# helper_tray_storage_station_v4.net
KiCad netlist of a schematic drawn in EAGLE
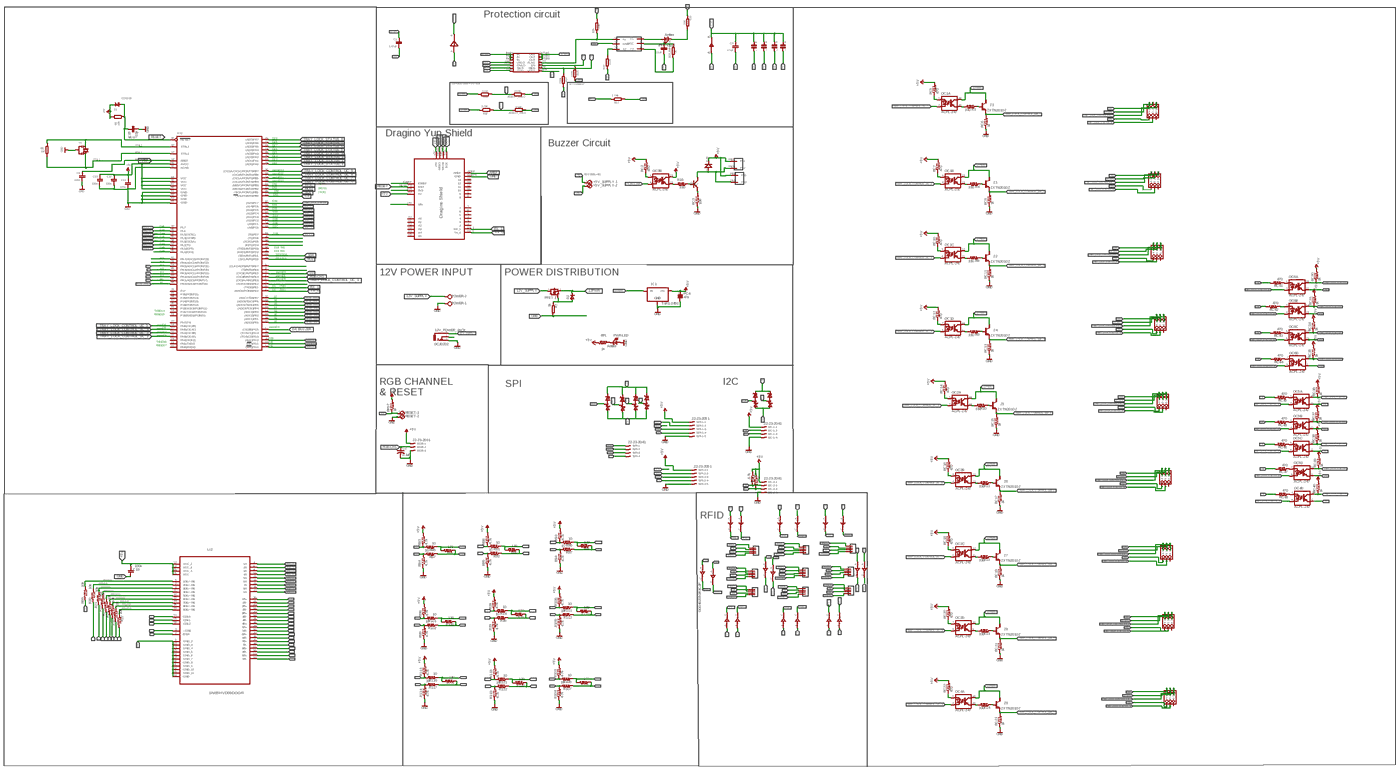
[diagram p0: schematic, sheet 1, overview]
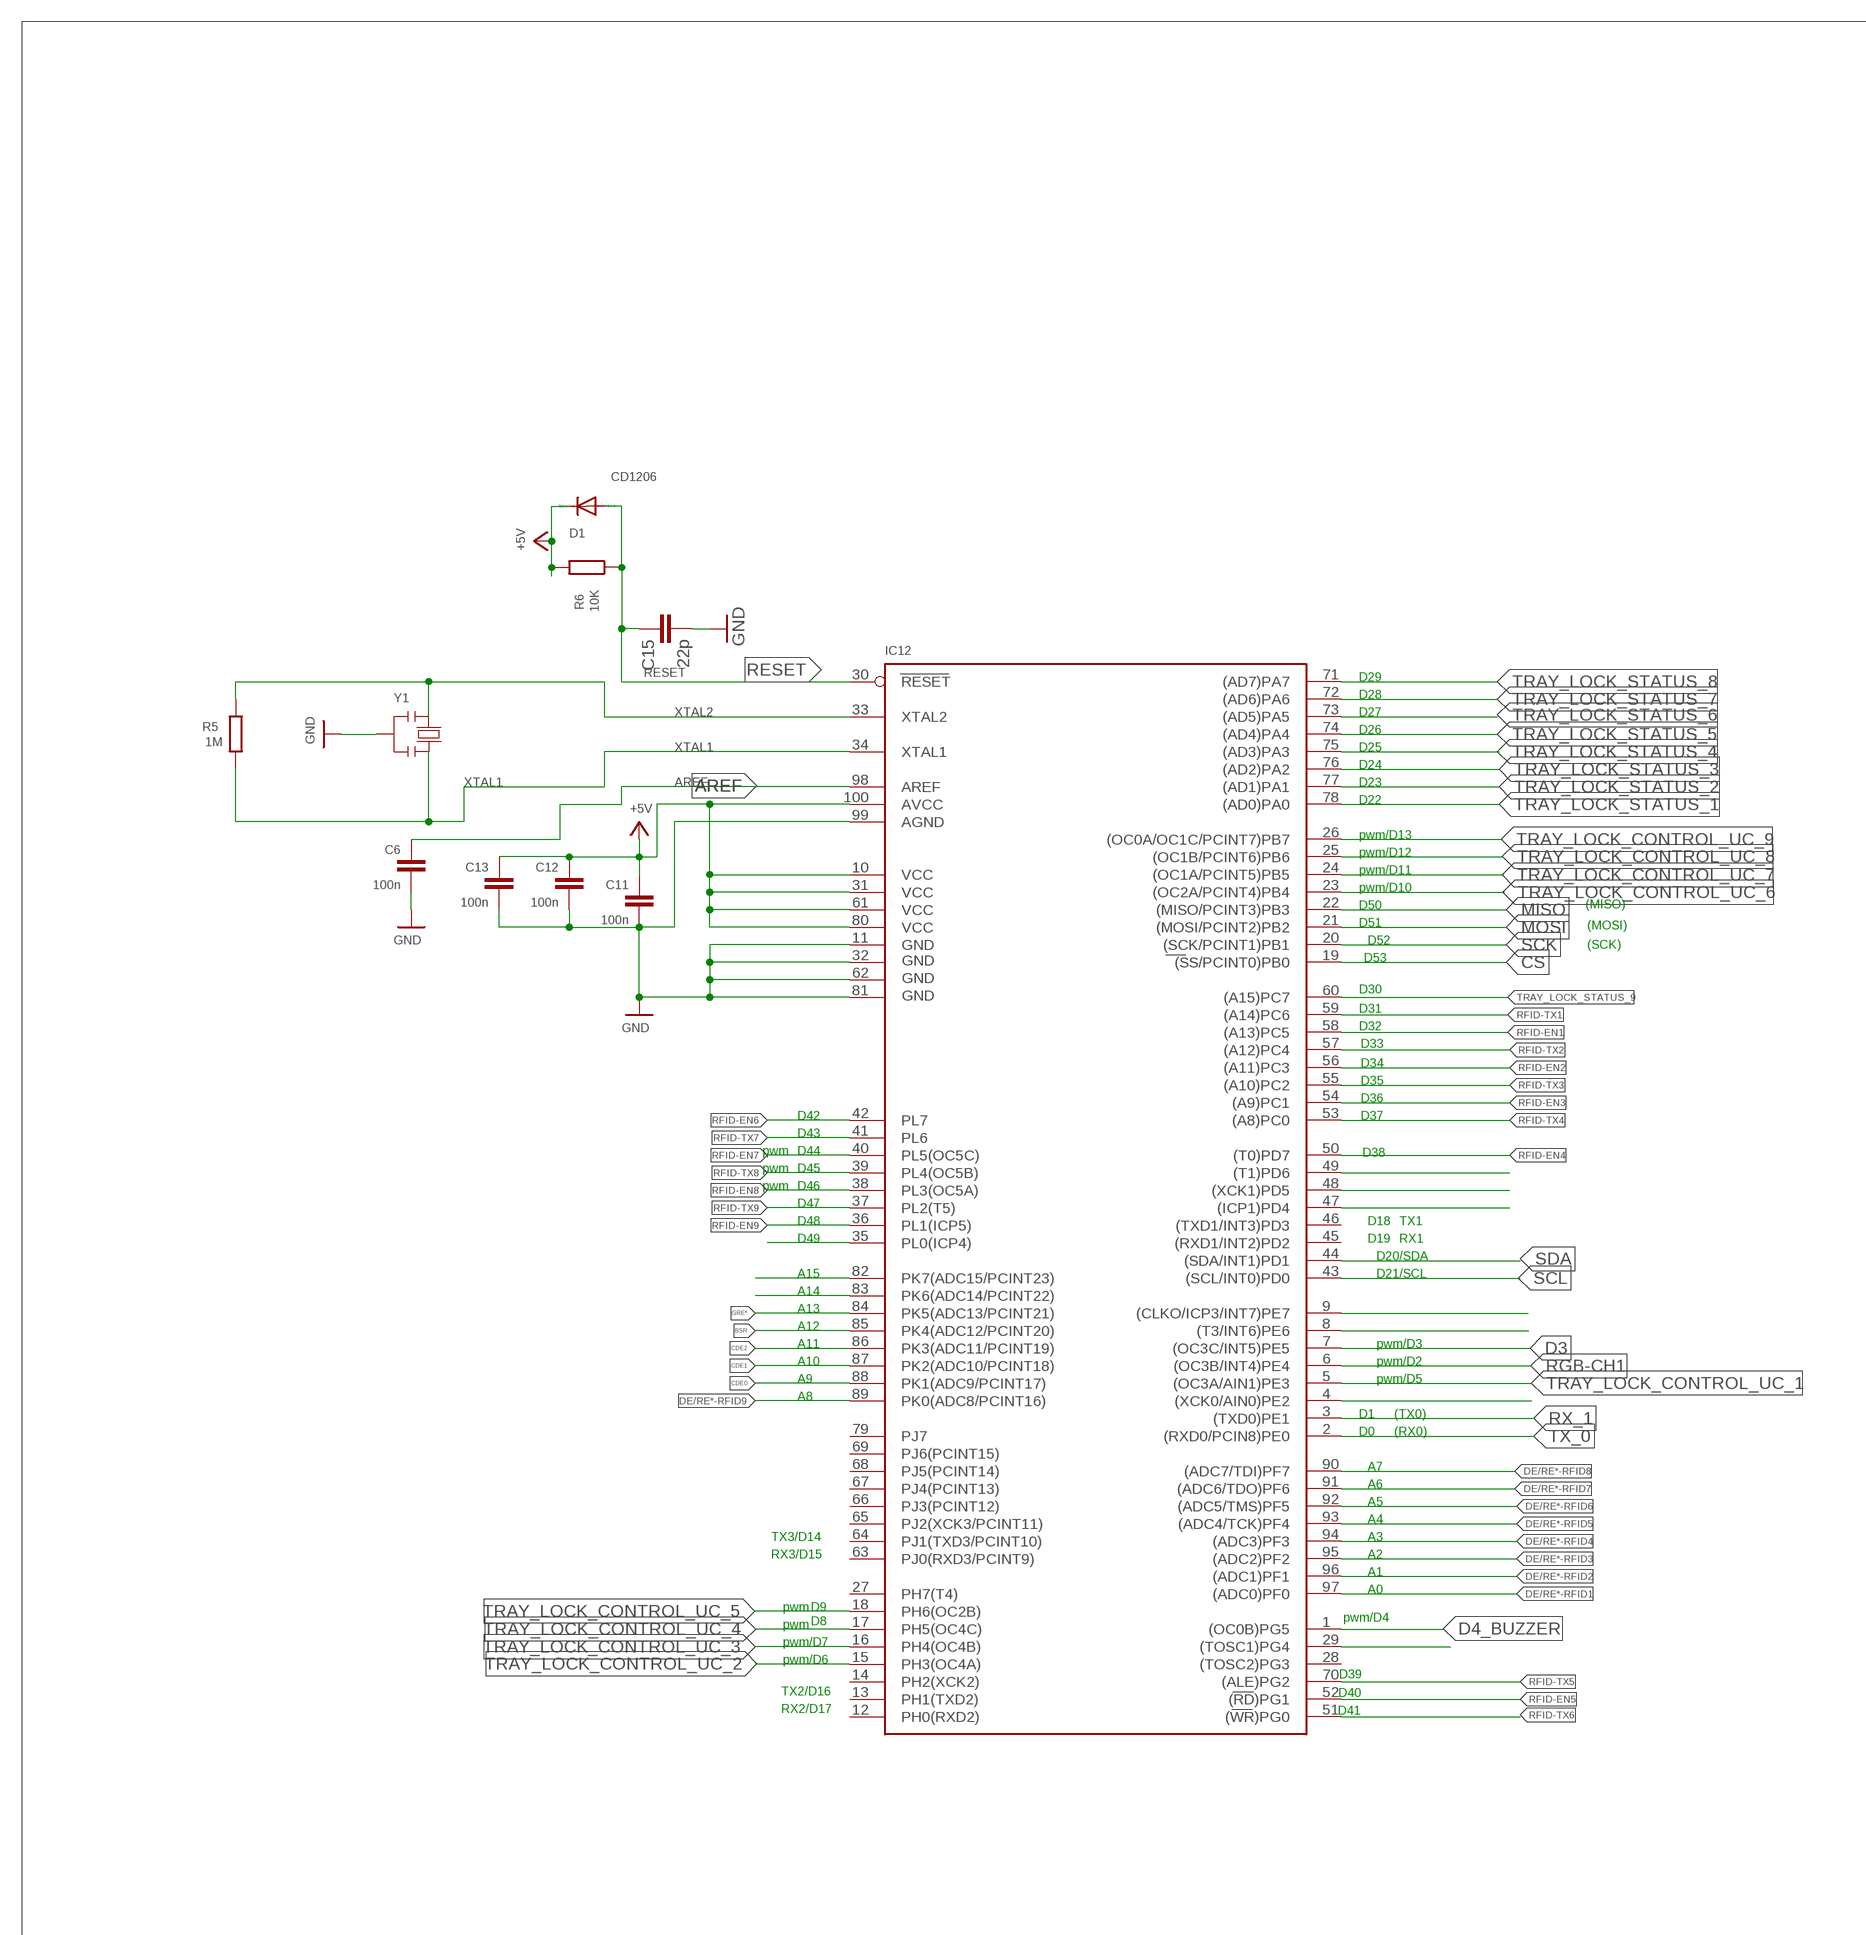
[diagram p1: schematic, sheet 1, part 1 of 6]
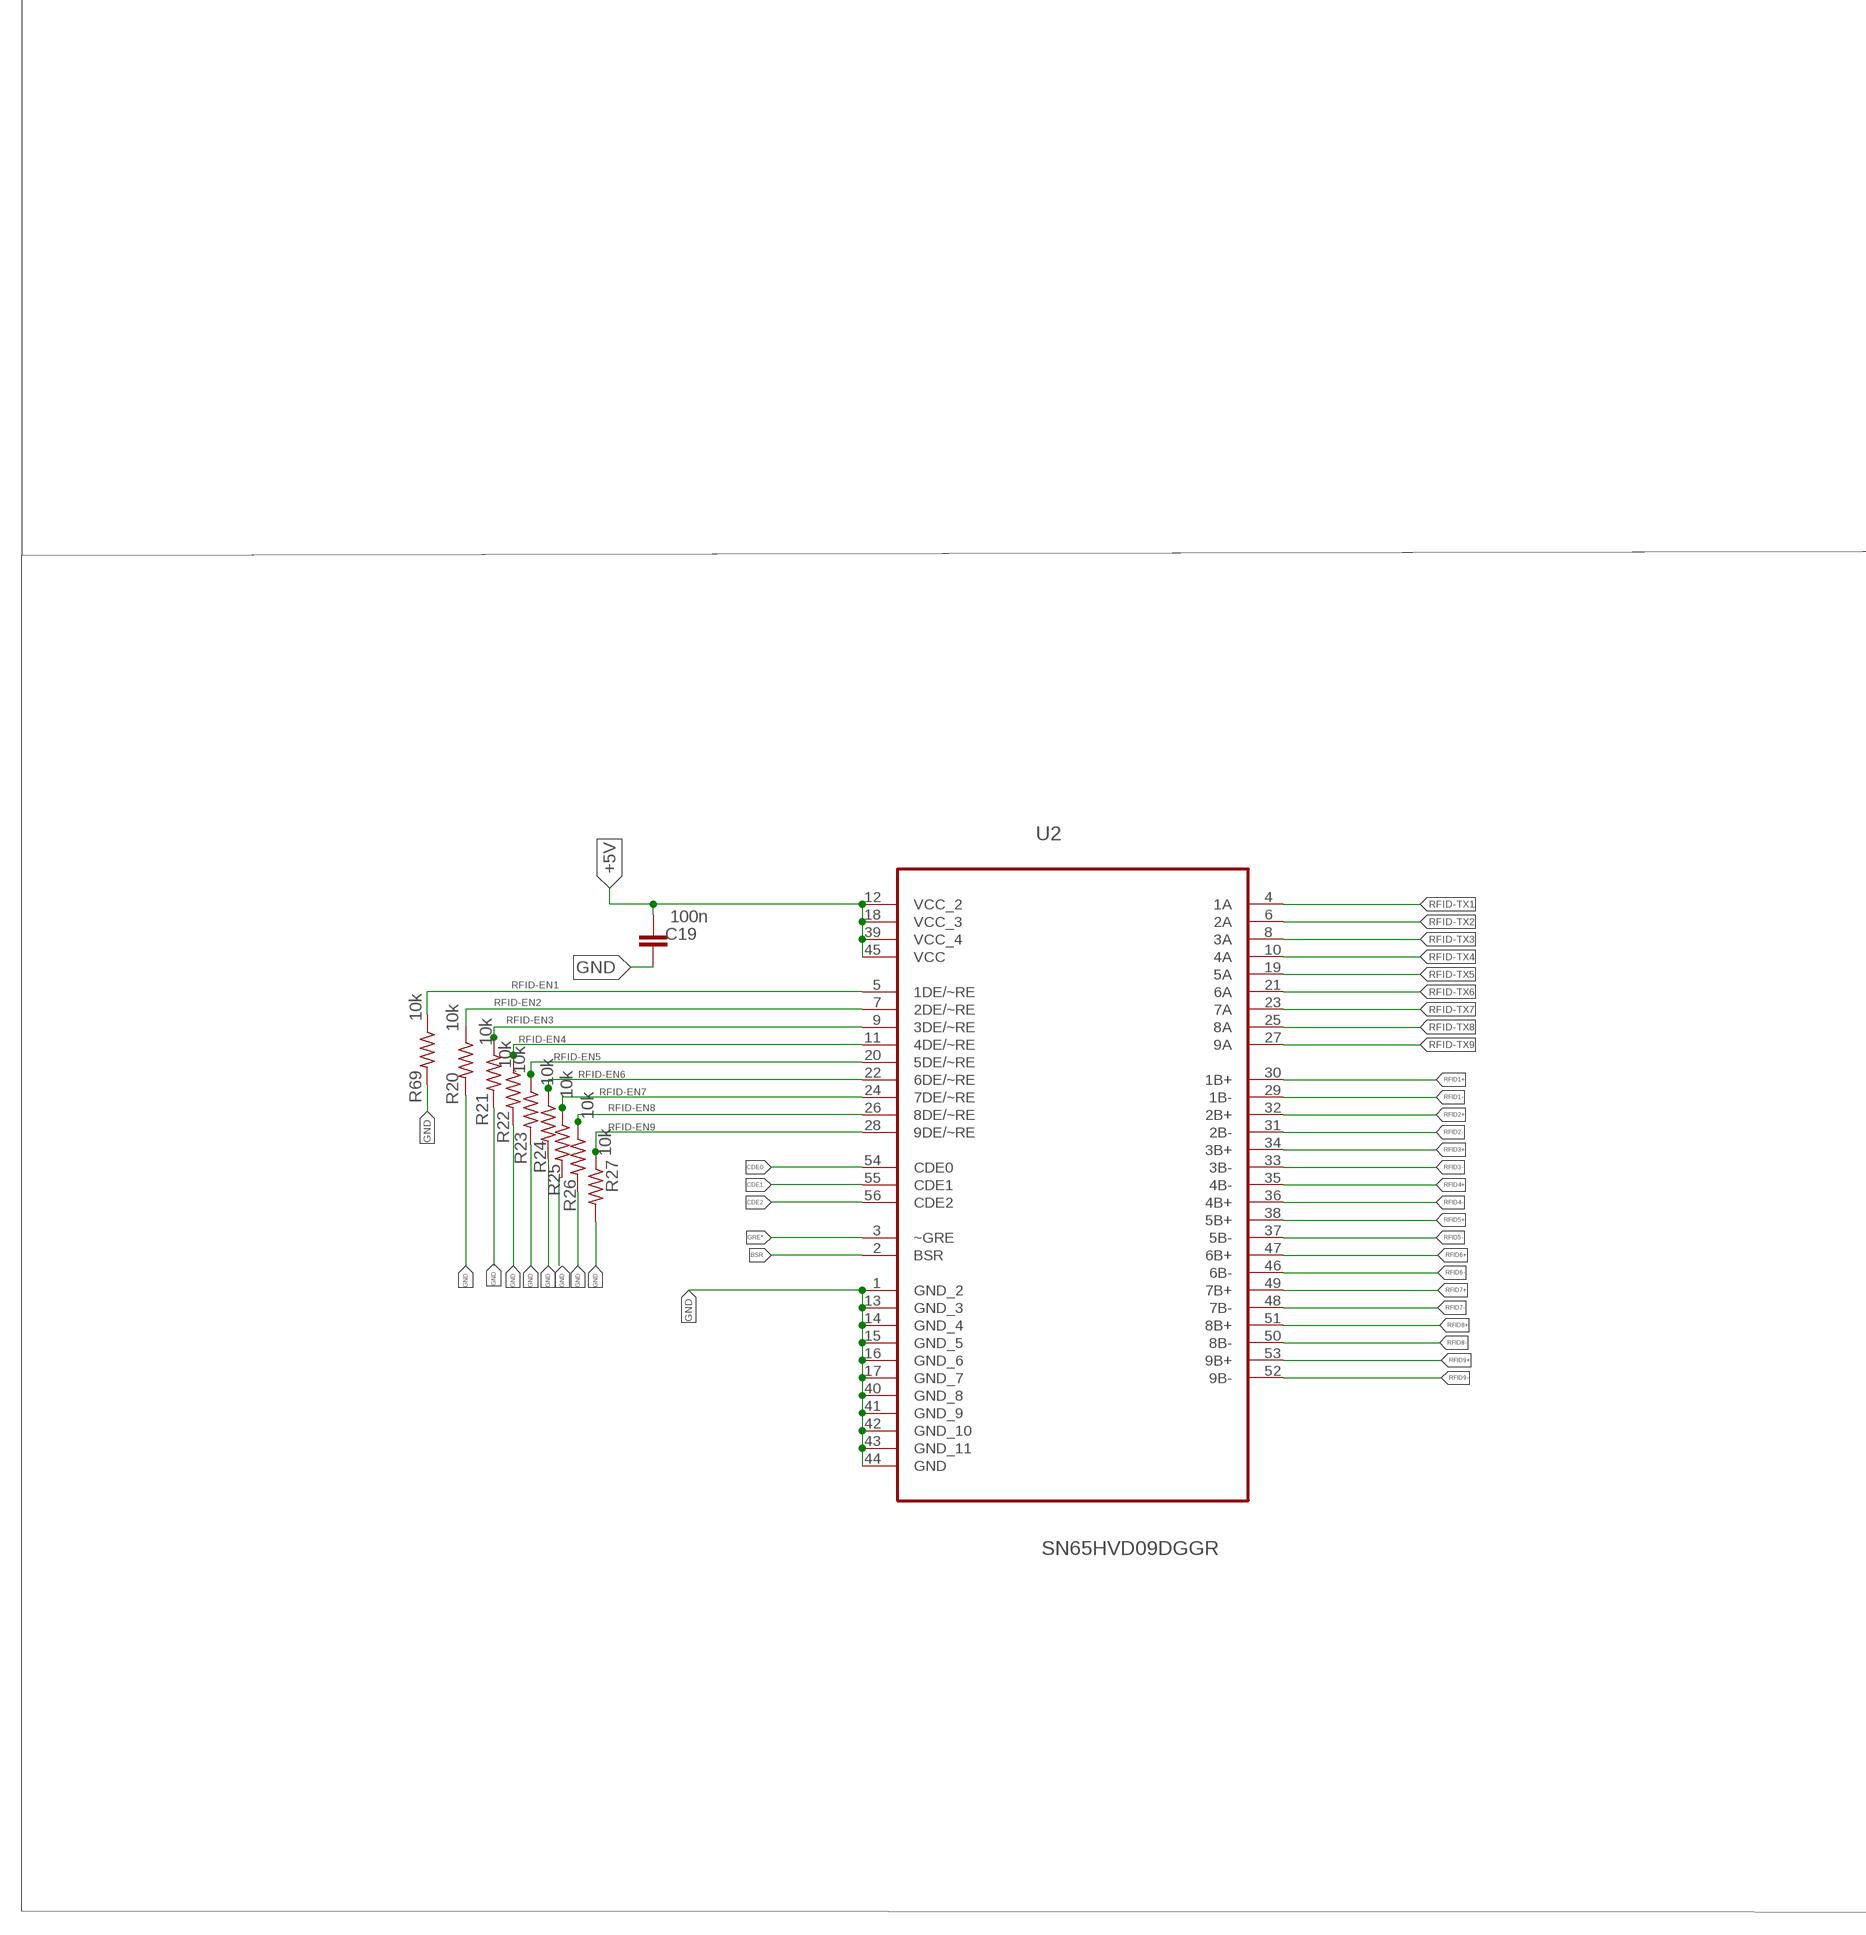
[diagram p2: schematic, sheet 1, part 2 of 6]
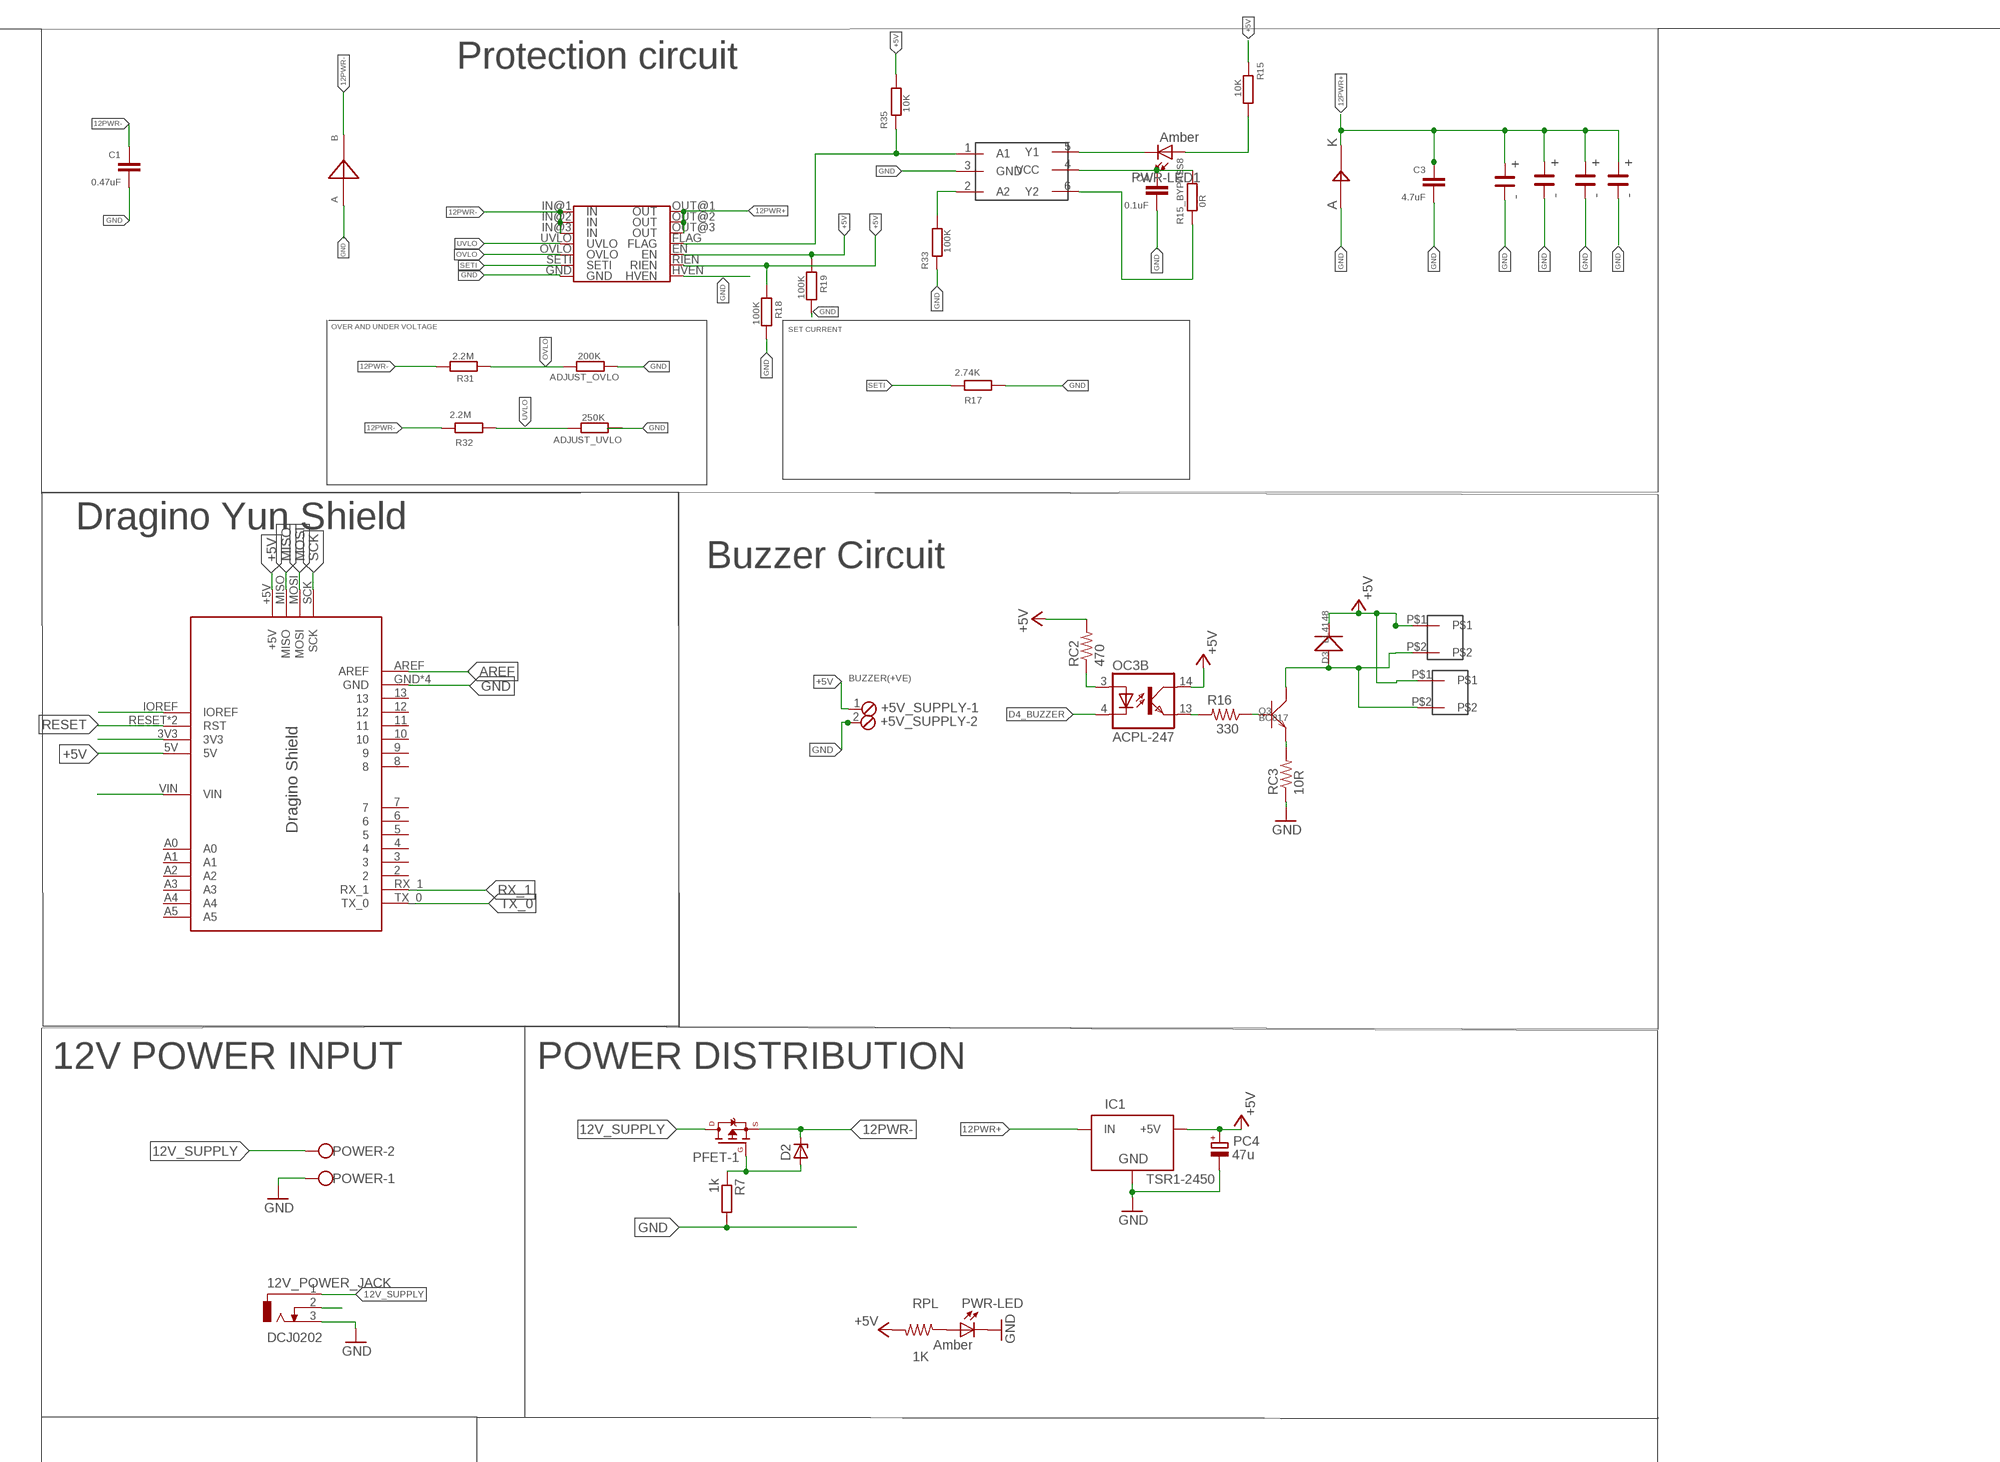
[diagram p3: schematic, sheet 1, part 3 of 6]
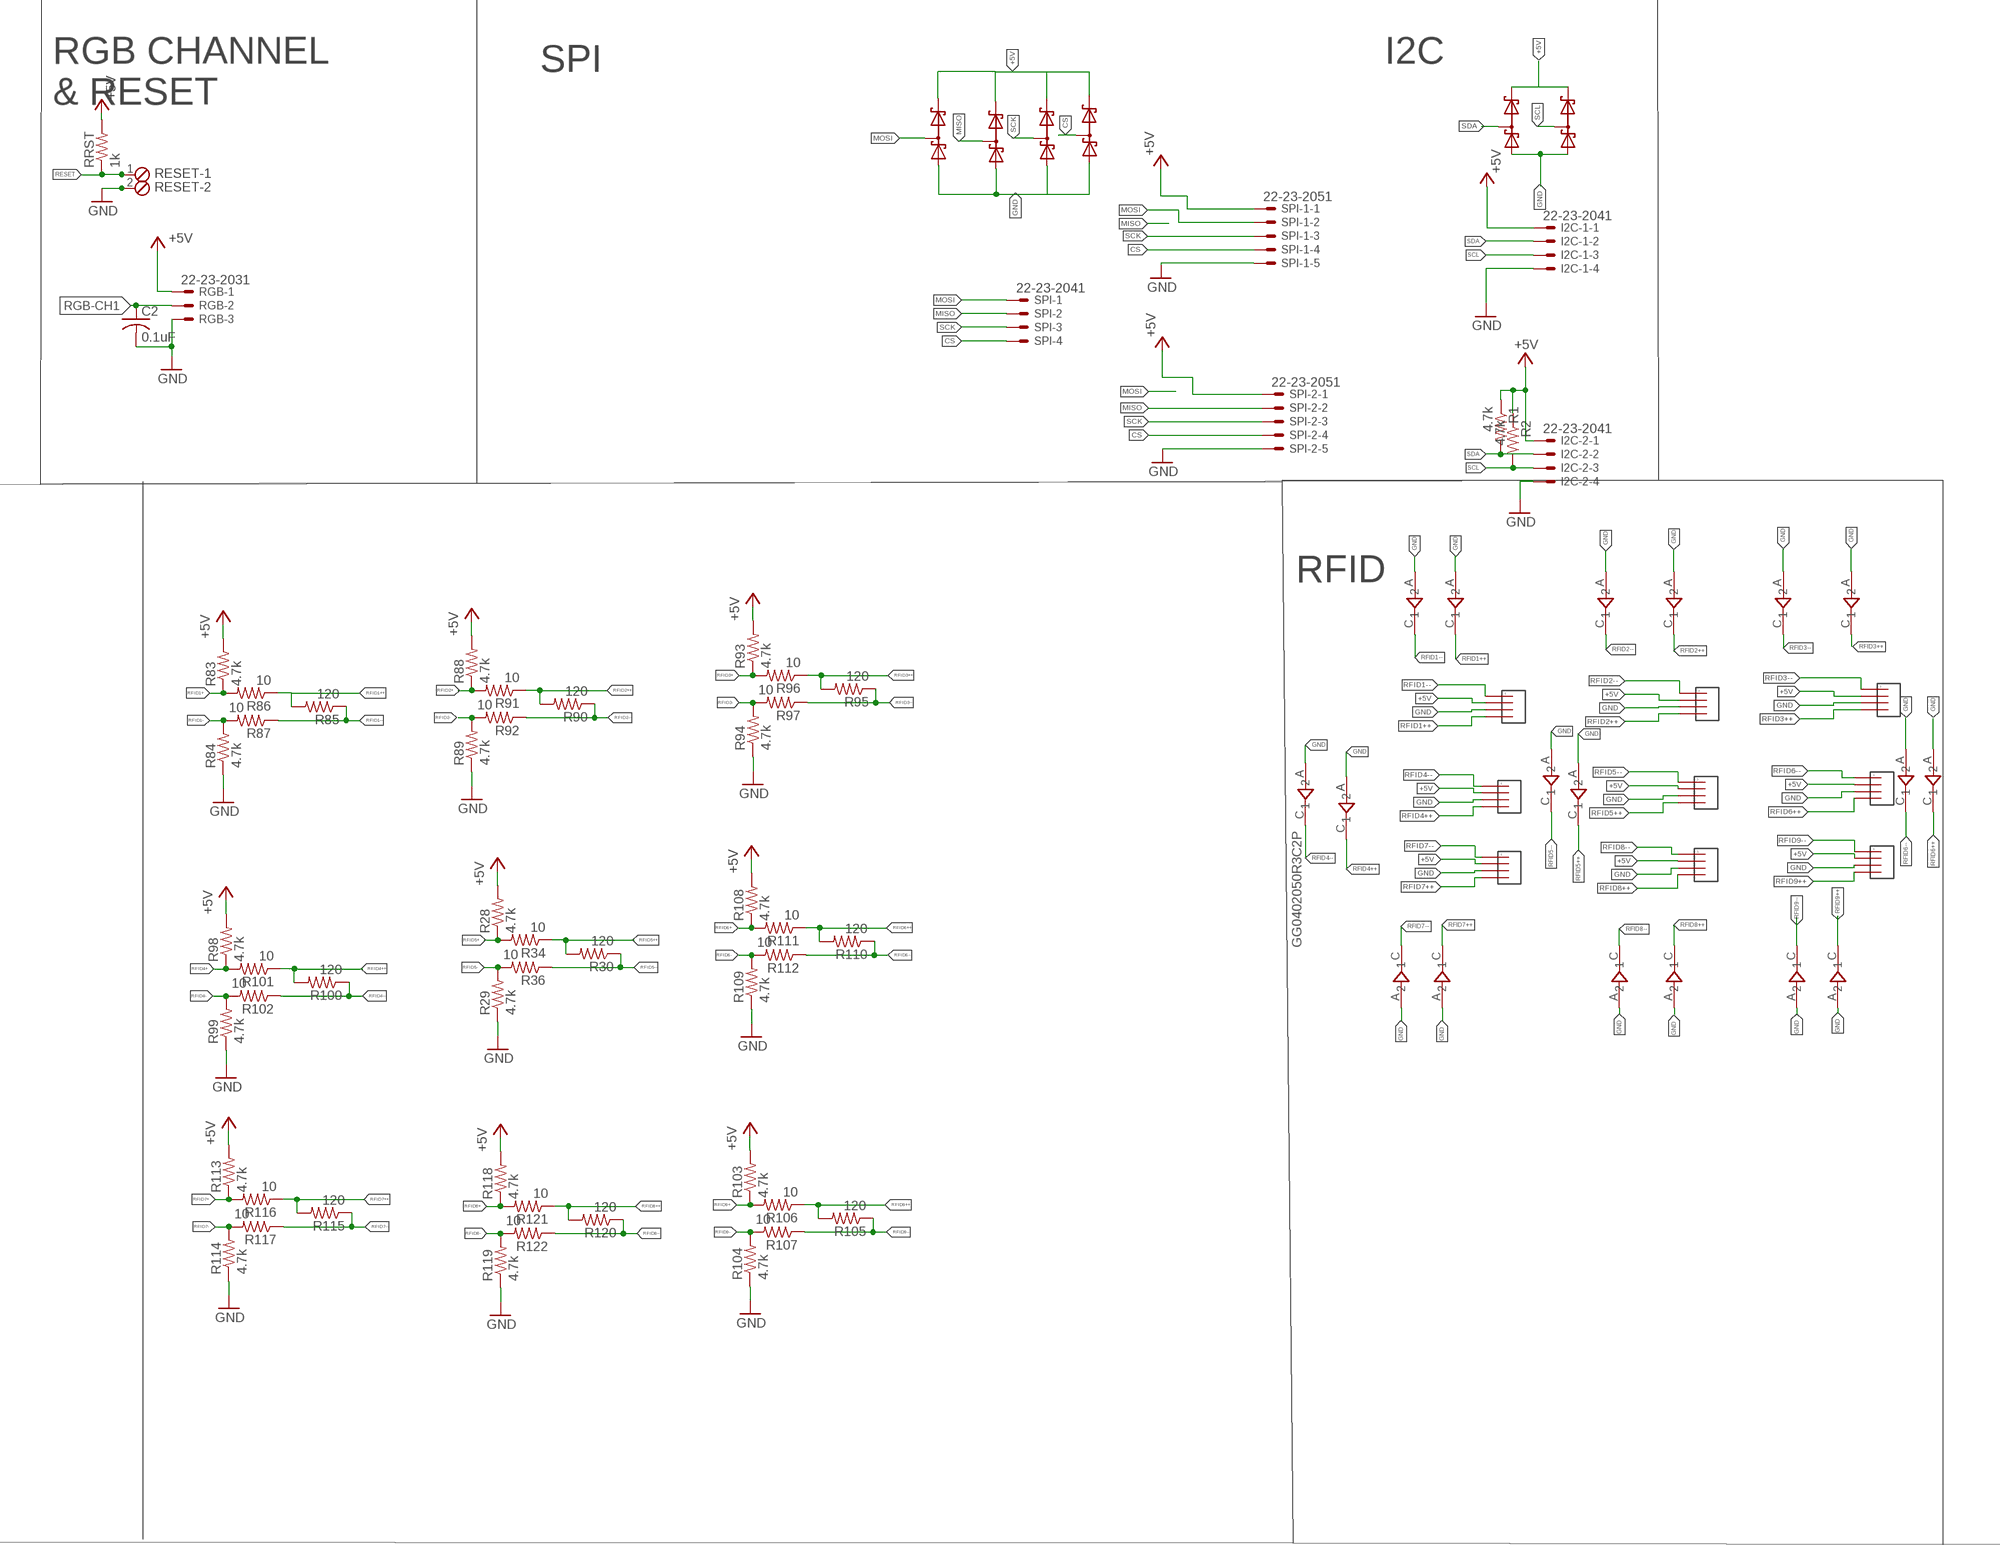
[diagram p4: schematic, sheet 1, part 4 of 6]
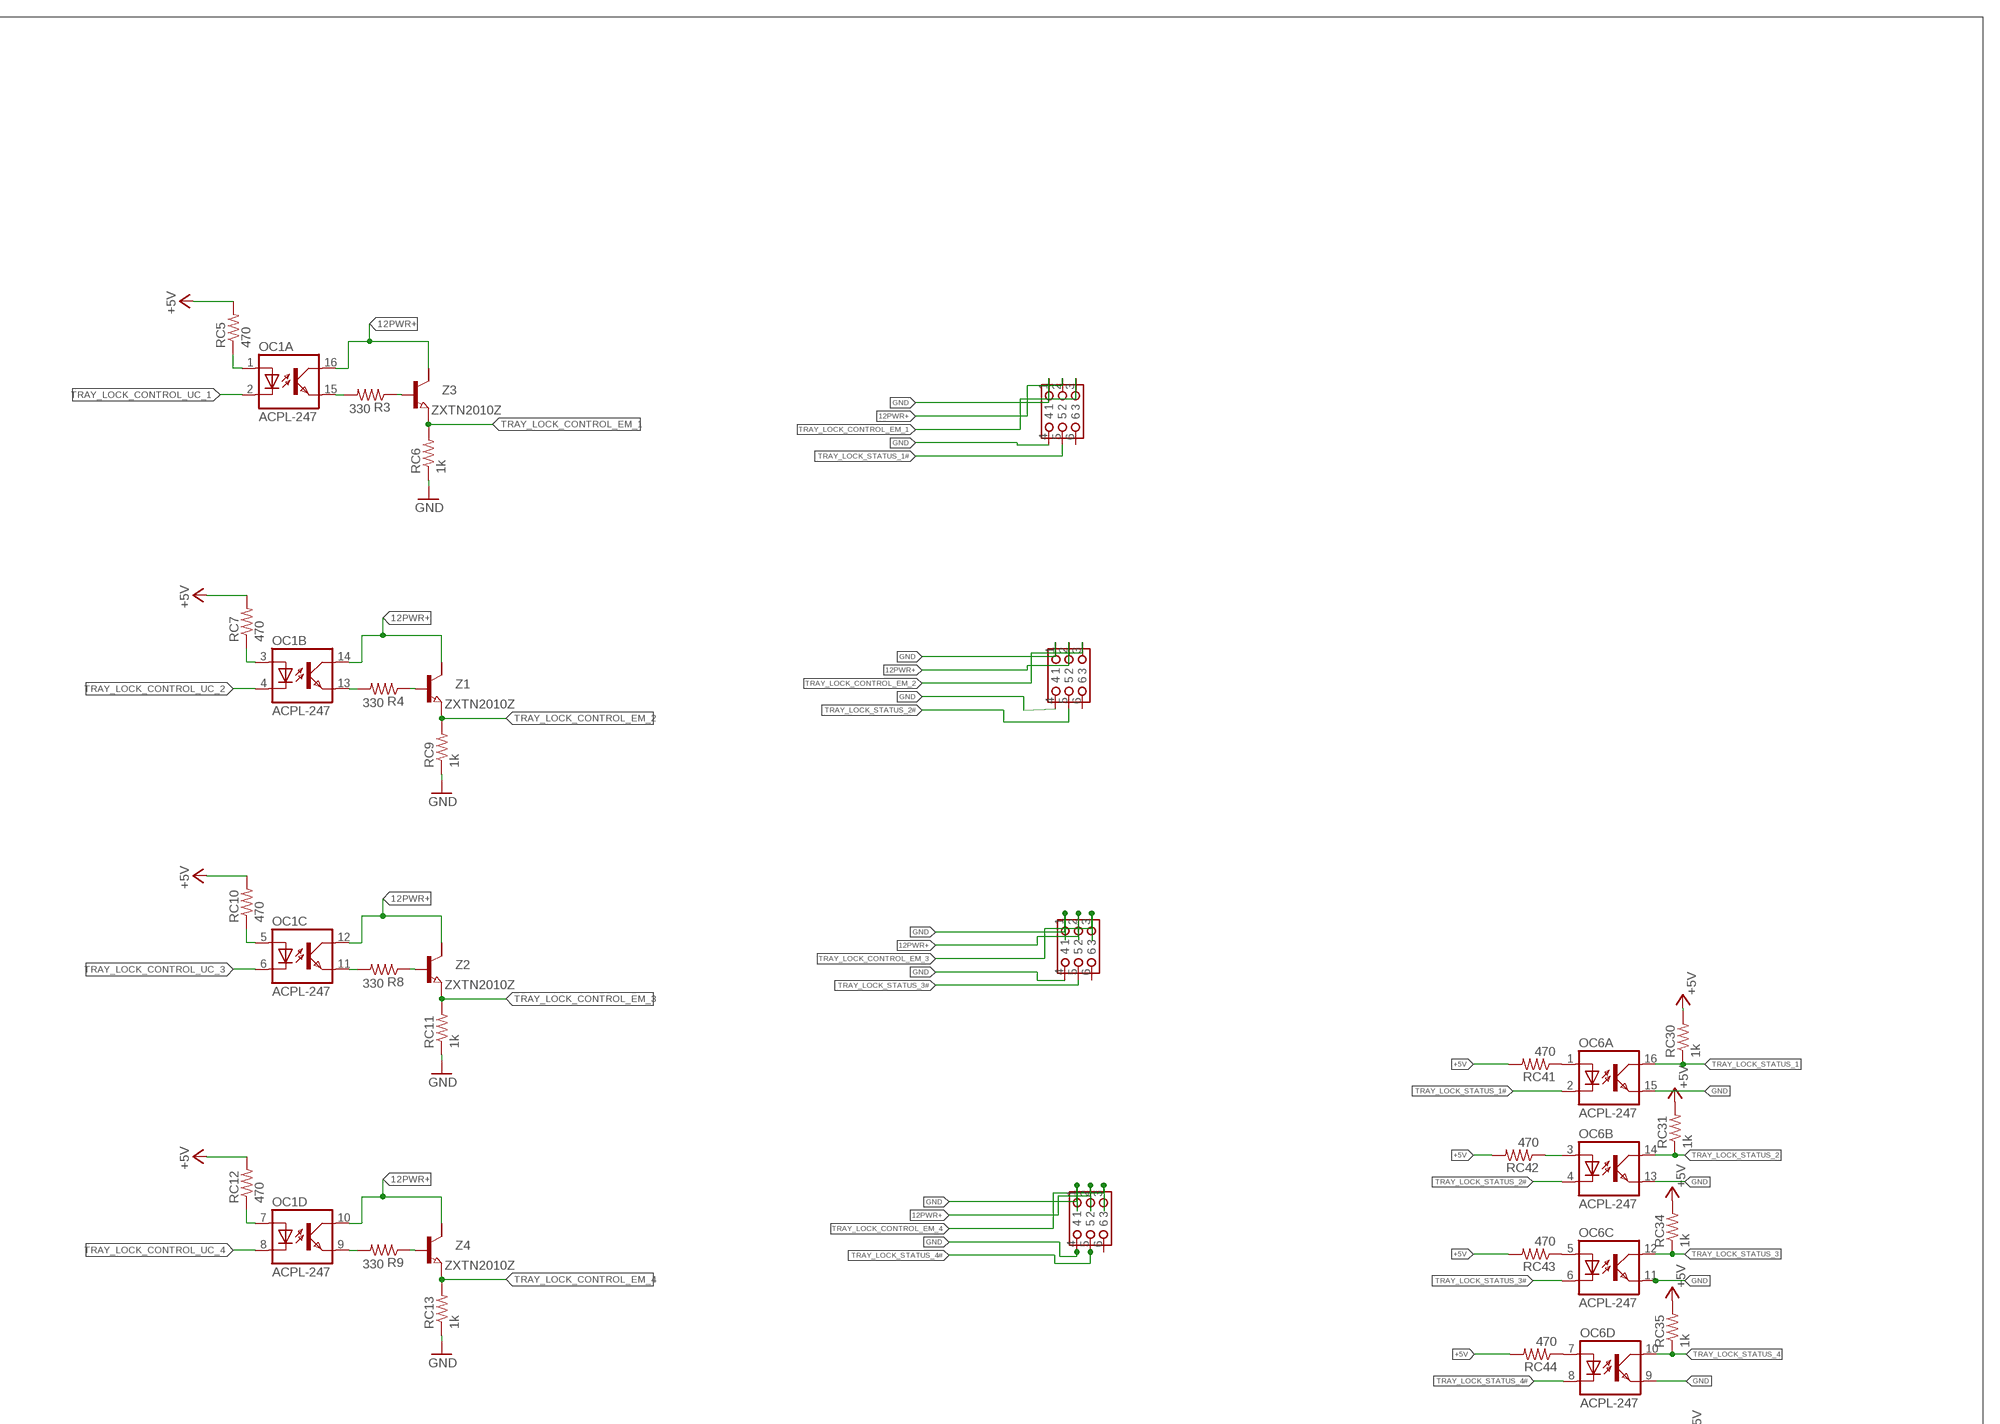
[diagram p5: schematic, sheet 1, part 5 of 6]
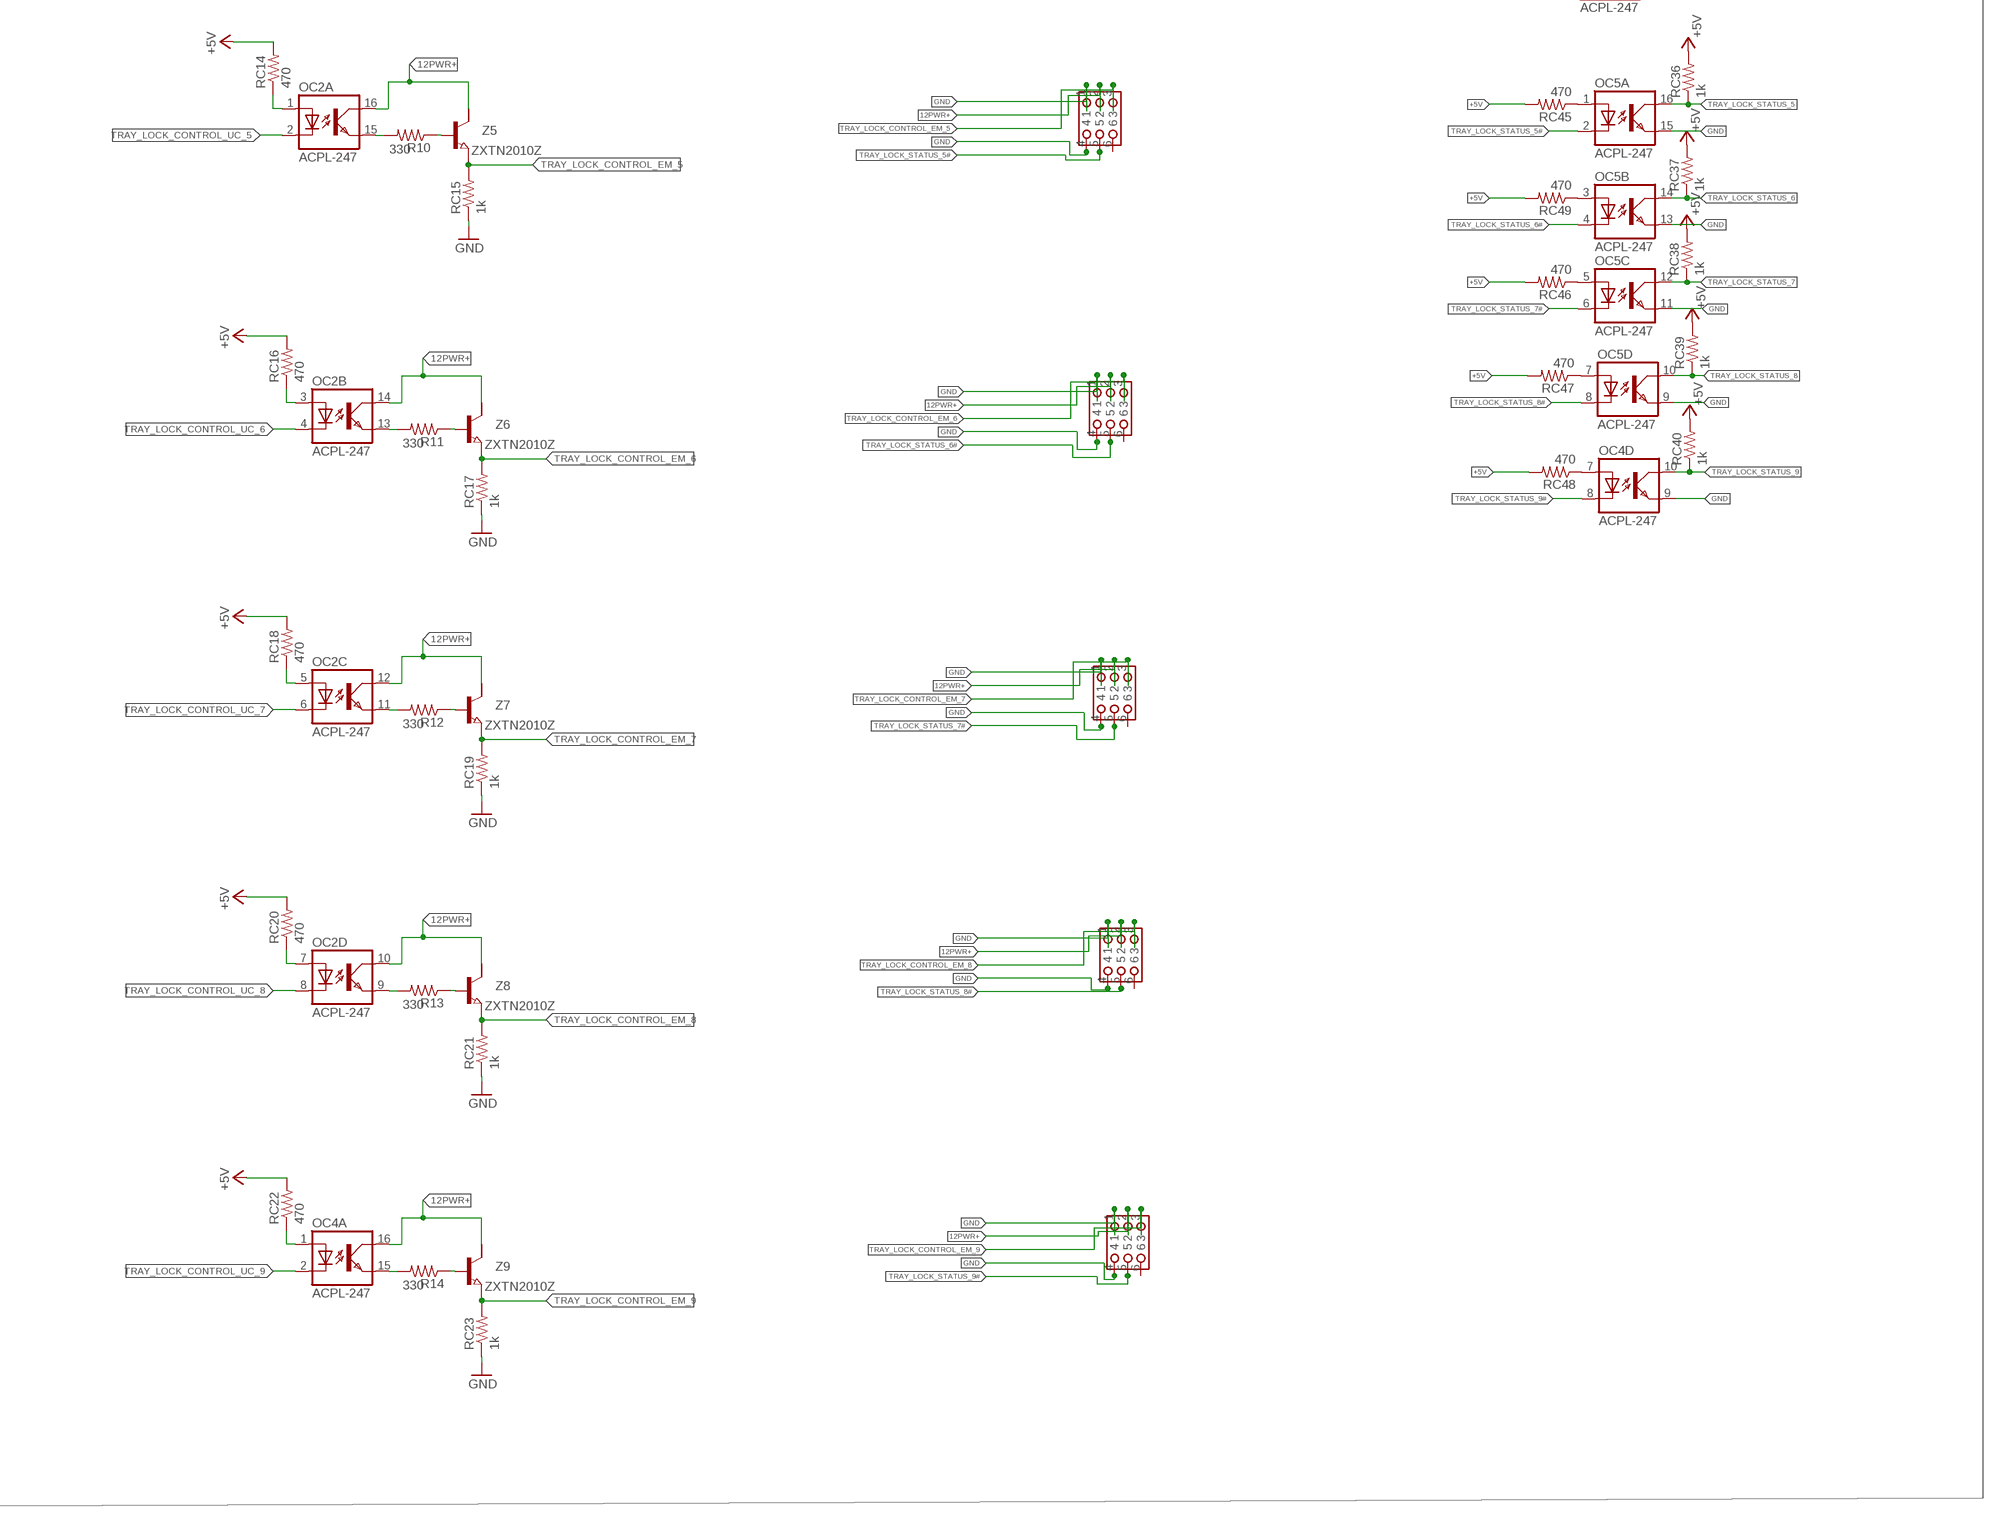
[diagram p6: schematic, sheet 1, part 6 of 6]

(export (version "E")
  (design (tool "Eeschema 10.0.6"))
  (components
    (comp (ref "+5V_SUPPLY")
      (value "MPT2")
      (footprint "eagle-import:2POL254")
      (libsource (lib "eagle-import") (part "MPT2"))
    )
    (comp (ref "12V_POWER_JACK")
      (value "DCJ0202")
      (footprint "eagle-import:DCJ0202")
      (libsource (lib "eagle-import") (part "DCJ0202"))
    )
    (comp (ref "ADJUST_OVLO")
      (value "200K")
      (footprint "eagle-import:R0603-ROUND")
      (libsource (lib "eagle-import") (part "R-EU_R0603"))
    )
    (comp (ref "ADJUST_UVLO")
      (value "250K")
      (footprint "eagle-import:R0603-ROUND")
      (libsource (lib "eagle-import") (part "R-EU_R0603"))
    )
    (comp (ref "C1")
      (value "0.47uF")
      (footprint "eagle-import:C0603-ROUND")
      (libsource (lib "eagle-import") (part "C-EU0603-RND"))
    )
    (comp (ref "C2")
      (value "0.1uF")
      (footprint "eagle-import:C0603K")
      (libsource (lib "eagle-import") (part "C-USC0603K"))
    )
    (comp (ref "C3")
      (value "4.7uF")
      (footprint "eagle-import:C0603-ROUND")
      (libsource (lib "eagle-import") (part "C-EU0603-RND"))
    )
    (comp (ref "C4")
      (value "0.1uF")
      (footprint "eagle-import:C0603-ROUND")
      (libsource (lib "eagle-import") (part "C-EU0603-RND"))
    )
    (comp (ref "C6")
      (value "100n")
      (footprint "eagle-import:C0603-ROUND")
      (libsource (lib "eagle-import") (part "C-EU0603-RND"))
    )
    (comp (ref "C11")
      (value "100n")
      (footprint "eagle-import:C0603-ROUND")
      (libsource (lib "eagle-import") (part "C-EU0603-RND"))
    )
    (comp (ref "C12")
      (value "100n")
      (footprint "eagle-import:C0603-ROUND")
      (libsource (lib "eagle-import") (part "C-EU0603-RND"))
    )
    (comp (ref "C13")
      (value "100n")
      (footprint "eagle-import:C0603-ROUND")
      (libsource (lib "eagle-import") (part "C-EU0603-RND"))
    )
    (comp (ref "C15")
      (value "22p")
      (footprint "eagle-import:C0603-ROUND")
      (libsource (lib "eagle-import") (part "C-EU0603-RND"))
    )
    (comp (ref "C19")
      (value "100n")
      (footprint "eagle-import:C0603-ROUND")
      (libsource (lib "eagle-import") (part "C-EU0603-RND"))
    )
    (comp (ref "D1")
      (value "CD1206")
      (footprint "eagle-import:MINIMELF")
      (libsource (lib "eagle-import") (part "DIODE-MINIMELF"))
    )
    (comp (ref "D2")
      (value "1SMA5925BT3G")
      (footprint "eagle-import:DO214AC")
      (fields (field (name "MF") "ON Semiconductor"))
      (libsource (lib "eagle-import") (part "1SMA59BT3G25"))
    )
    (comp (ref "D3")
      (value "LL4148")
      (footprint "eagle-import:LL-34")
      (libsource (lib "eagle-import") (part "D'1N4148-SMD'"))
    )
    (comp (ref "I2C-1")
      (value "22-23-2041")
      (footprint "eagle-import:22-23-2041")
      (fields (field (name "MF") "MOLEX"))
      (libsource (lib "eagle-import") (part "22-23-2041"))
    )
    (comp (ref "I2C-2")
      (value "22-23-2041")
      (footprint "eagle-import:22-23-2041")
      (fields (field (name "MF") "MOLEX"))
      (libsource (lib "eagle-import") (part "22-23-2041"))
    )
    (comp (ref "IC1")
      (value "TSR1-2450")
      (footprint "eagle-import:TSR-1")
      (libsource (lib "eagle-import") (part "TSR1-2450"))
    )
    (comp (ref "IC12")
      (value "ATMEGA25602560-16AU")
      (footprint "eagle-import:TQFP100")
      (libsource (lib "eagle-import") (part "ATMEGA2560AU2560-16"))
    )
    (comp (ref "OC1")
      (value "ACPL-247")
      (footprint "eagle-import:SOP16")
      (libsource (lib "eagle-import") (part "ACPL-247"))
    )
    (comp (ref "OC2")
      (value "ACPL-247")
      (footprint "eagle-import:SOP16")
      (libsource (lib "eagle-import") (part "ACPL-247"))
    )
    (comp (ref "OC3")
      (value "ACPL-247")
      (footprint "eagle-import:SOP16")
      (libsource (lib "eagle-import") (part "ACPL-247"))
    )
    (comp (ref "OC4")
      (value "ACPL-247")
      (footprint "eagle-import:SOP16")
      (libsource (lib "eagle-import") (part "ACPL-247"))
    )
    (comp (ref "OC5")
      (value "ACPL-247")
      (footprint "eagle-import:SOP16")
      (libsource (lib "eagle-import") (part "ACPL-247"))
    )
    (comp (ref "OC6")
      (value "ACPL-247")
      (footprint "eagle-import:SOP16")
      (libsource (lib "eagle-import") (part "ACPL-247"))
    )
    (comp (ref "PC4")
      (value "47u")
      (footprint "eagle-import:PANASONIC_D")
      (libsource (lib "eagle-import") (part "CPOL-EUD"))
    )
    (comp (ref "PFET-1")
      (value "FQP47P06NORMAL")
      (footprint "eagle-import:FQP47P06-NORMAL")
      (libsource (lib "eagle-import") (part "FQP47P06NORMAL"))
    )
    (comp (ref "POWER")
      (value "W237-102")
      (footprint "eagle-import:W237-102")
      (fields (field (name "MPN") "237-102"))
      (libsource (lib "eagle-import") (part "W237-102"))
    )
    (comp (ref "PWR-LED")
      (value "Amber")
      (footprint "eagle-import:LED-0603")
      (libsource (lib "eagle-import") (part "LED0603"))
    )
    (comp (ref "PWR-LED1")
      (value "Amber")
      (footprint "eagle-import:LED-0603")
      (libsource (lib "eagle-import") (part "LED0603"))
    )
    (comp (ref "Q3")
      (value "BC817")
      (footprint "eagle-import:SOT23")
      (libsource (lib "eagle-import") (part "TRANSISTOR-NPN-SOT23"))
    )
    (comp (ref "R1")
      (value "4.7k")
      (footprint "eagle-import:0603-RES")
      (libsource (lib "eagle-import") (part "RESISTOR0603-RES"))
    )
    (comp (ref "R2")
      (value "4.7k")
      (footprint "eagle-import:0603-RES")
      (libsource (lib "eagle-import") (part "RESISTOR0603-RES"))
    )
    (comp (ref "R3")
      (value "330")
      (footprint "eagle-import:R0603")
      (libsource (lib "eagle-import") (part "R-US_R0603"))
    )
    (comp (ref "R4")
      (value "330")
      (footprint "eagle-import:R0603")
      (libsource (lib "eagle-import") (part "R-US_R0603"))
    )
    (comp (ref "R5")
      (value "1M")
      (footprint "eagle-import:R0603-ROUND")
      (libsource (lib "eagle-import") (part "R-EU_R0603"))
    )
    (comp (ref "R6")
      (value "10K")
      (footprint "eagle-import:R0603-ROUND")
      (libsource (lib "eagle-import") (part "R-EU_R0603"))
    )
    (comp (ref "R7")
      (value "1k")
      (footprint "eagle-import:R0603")
      (libsource (lib "eagle-import") (part "resistor_R-EU_R0603"))
    )
    (comp (ref "R8")
      (value "330")
      (footprint "eagle-import:R0603")
      (libsource (lib "eagle-import") (part "R-US_R0603"))
    )
    (comp (ref "R9")
      (value "330")
      (footprint "eagle-import:R0603")
      (libsource (lib "eagle-import") (part "R-US_R0603"))
    )
    (comp (ref "R10")
      (value "330")
      (footprint "eagle-import:R0603")
      (libsource (lib "eagle-import") (part "R-US_R0603"))
    )
    (comp (ref "R11")
      (value "330")
      (footprint "eagle-import:R0603")
      (libsource (lib "eagle-import") (part "R-US_R0603"))
    )
    (comp (ref "R12")
      (value "330")
      (footprint "eagle-import:R0603")
      (libsource (lib "eagle-import") (part "R-US_R0603"))
    )
    (comp (ref "R13")
      (value "330")
      (footprint "eagle-import:R0603")
      (libsource (lib "eagle-import") (part "R-US_R0603"))
    )
    (comp (ref "R14")
      (value "330")
      (footprint "eagle-import:R0603")
      (libsource (lib "eagle-import") (part "R-US_R0603"))
    )
    (comp (ref "R15")
      (value "10K")
      (footprint "eagle-import:R0603-ROUND")
      (libsource (lib "eagle-import") (part "R-EU_R0603"))
    )
    (comp (ref "R15_BYPASS8")
      (value "0R")
      (footprint "eagle-import:R0603-ROUND")
      (libsource (lib "eagle-import") (part "R-EU_R0603"))
    )
    (comp (ref "R16")
      (value "330")
      (footprint "eagle-import:R0603")
      (libsource (lib "eagle-import") (part "R-US_R0603"))
    )
    (comp (ref "R17")
      (value "2.74K")
      (footprint "eagle-import:R0603-ROUND")
      (libsource (lib "eagle-import") (part "R-EU_R0603"))
    )
    (comp (ref "R18")
      (value "100K")
      (footprint "eagle-import:R0603-ROUND")
      (libsource (lib "eagle-import") (part "R-EU_R0603"))
    )
    (comp (ref "R19")
      (value "100K")
      (footprint "eagle-import:R0603-ROUND")
      (libsource (lib "eagle-import") (part "R-EU_R0603"))
    )
    (comp (ref "R20")
      (value "10k")
      (footprint "eagle-import:R0603")
      (libsource (lib "eagle-import") (part "R-US_R0603"))
    )
    (comp (ref "R21")
      (value "10k")
      (footprint "eagle-import:R0603")
      (libsource (lib "eagle-import") (part "R-US_R0603"))
    )
    (comp (ref "R22")
      (value "10k")
      (footprint "eagle-import:R0603")
      (libsource (lib "eagle-import") (part "R-US_R0603"))
    )
    (comp (ref "R23")
      (value "10k")
      (footprint "eagle-import:R0603")
      (libsource (lib "eagle-import") (part "R-US_R0603"))
    )
    (comp (ref "R24")
      (value "10k")
      (footprint "eagle-import:R0603")
      (libsource (lib "eagle-import") (part "R-US_R0603"))
    )
    (comp (ref "R25")
      (value "10k")
      (footprint "eagle-import:R0603")
      (libsource (lib "eagle-import") (part "R-US_R0603"))
    )
    (comp (ref "R26")
      (value "10k")
      (footprint "eagle-import:R0603")
      (libsource (lib "eagle-import") (part "R-US_R0603"))
    )
    (comp (ref "R27")
      (value "10k")
      (footprint "eagle-import:R0603")
      (libsource (lib "eagle-import") (part "R-US_R0603"))
    )
    (comp (ref "R28")
      (value "4.7k")
      (footprint "eagle-import:R0603")
      (libsource (lib "eagle-import") (part "R-US_R0603"))
    )
    (comp (ref "R29")
      (value "4.7k")
      (footprint "eagle-import:R0603")
      (libsource (lib "eagle-import") (part "R-US_R0603"))
    )
    (comp (ref "R30")
      (value "120")
      (footprint "eagle-import:R0603")
      (libsource (lib "eagle-import") (part "R-US_R0603"))
    )
    (comp (ref "R31")
      (value "2.2M")
      (footprint "eagle-import:R0603-ROUND")
      (libsource (lib "eagle-import") (part "R-EU_R0603"))
    )
    (comp (ref "R32")
      (value "2.2M")
      (footprint "eagle-import:R0603-ROUND")
      (libsource (lib "eagle-import") (part "R-EU_R0603"))
    )
    (comp (ref "R33")
      (value "100K")
      (footprint "eagle-import:R0603-ROUND")
      (libsource (lib "eagle-import") (part "R-EU_R0603"))
    )
    (comp (ref "R34")
      (value "10")
      (footprint "eagle-import:R0603")
      (libsource (lib "eagle-import") (part "R-US_R0603"))
    )
    (comp (ref "R35")
      (value "10K")
      (footprint "eagle-import:R0603-ROUND")
      (libsource (lib "eagle-import") (part "R-EU_R0603"))
    )
    (comp (ref "R36")
      (value "10")
      (footprint "eagle-import:R0603")
      (libsource (lib "eagle-import") (part "R-US_R0603"))
    )
    (comp (ref "R69")
      (value "10k")
      (footprint "eagle-import:R0603")
      (libsource (lib "eagle-import") (part "R-US_R0603"))
    )
    (comp (ref "R83")
      (value "4.7k")
      (footprint "eagle-import:R0603")
      (libsource (lib "eagle-import") (part "R-US_R0603"))
    )
    (comp (ref "R84")
      (value "4.7k")
      (footprint "eagle-import:R0603")
      (libsource (lib "eagle-import") (part "R-US_R0603"))
    )
    (comp (ref "R85")
      (value "120")
      (footprint "eagle-import:R0603")
      (libsource (lib "eagle-import") (part "R-US_R0603"))
    )
    (comp (ref "R86")
      (value "10")
      (footprint "eagle-import:R0603")
      (libsource (lib "eagle-import") (part "R-US_R0603"))
    )
    (comp (ref "R87")
      (value "10")
      (footprint "eagle-import:R0603")
      (libsource (lib "eagle-import") (part "R-US_R0603"))
    )
    (comp (ref "R88")
      (value "4.7k")
      (footprint "eagle-import:R0603")
      (libsource (lib "eagle-import") (part "R-US_R0603"))
    )
    (comp (ref "R89")
      (value "4.7k")
      (footprint "eagle-import:R0603")
      (libsource (lib "eagle-import") (part "R-US_R0603"))
    )
    (comp (ref "R90")
      (value "120")
      (footprint "eagle-import:R0603")
      (libsource (lib "eagle-import") (part "R-US_R0603"))
    )
    (comp (ref "R91")
      (value "10")
      (footprint "eagle-import:R0603")
      (libsource (lib "eagle-import") (part "R-US_R0603"))
    )
    (comp (ref "R92")
      (value "10")
      (footprint "eagle-import:R0603")
      (libsource (lib "eagle-import") (part "R-US_R0603"))
    )
    (comp (ref "R93")
      (value "4.7k")
      (footprint "eagle-import:R0603")
      (libsource (lib "eagle-import") (part "R-US_R0603"))
    )
    (comp (ref "R94")
      (value "4.7k")
      (footprint "eagle-import:R0603")
      (libsource (lib "eagle-import") (part "R-US_R0603"))
    )
    (comp (ref "R95")
      (value "120")
      (footprint "eagle-import:R0603")
      (libsource (lib "eagle-import") (part "R-US_R0603"))
    )
    (comp (ref "R96")
      (value "10")
      (footprint "eagle-import:R0603")
      (libsource (lib "eagle-import") (part "R-US_R0603"))
    )
    (comp (ref "R97")
      (value "10")
      (footprint "eagle-import:R0603")
      (libsource (lib "eagle-import") (part "R-US_R0603"))
    )
    (comp (ref "R98")
      (value "4.7k")
      (footprint "eagle-import:R0603")
      (libsource (lib "eagle-import") (part "R-US_R0603"))
    )
    (comp (ref "R99")
      (value "4.7k")
      (footprint "eagle-import:R0603")
      (libsource (lib "eagle-import") (part "R-US_R0603"))
    )
    (comp (ref "R100")
      (value "120")
      (footprint "eagle-import:R0603")
      (libsource (lib "eagle-import") (part "R-US_R0603"))
    )
    (comp (ref "R101")
      (value "10")
      (footprint "eagle-import:R0603")
      (libsource (lib "eagle-import") (part "R-US_R0603"))
    )
    (comp (ref "R102")
      (value "10")
      (footprint "eagle-import:R0603")
      (libsource (lib "eagle-import") (part "R-US_R0603"))
    )
    (comp (ref "R103")
      (value "4.7k")
      (footprint "eagle-import:R0603")
      (libsource (lib "eagle-import") (part "R-US_R0603"))
    )
    (comp (ref "R104")
      (value "4.7k")
      (footprint "eagle-import:R0603")
      (libsource (lib "eagle-import") (part "R-US_R0603"))
    )
    (comp (ref "R105")
      (value "120")
      (footprint "eagle-import:R0603")
      (libsource (lib "eagle-import") (part "R-US_R0603"))
    )
    (comp (ref "R106")
      (value "10")
      (footprint "eagle-import:R0603")
      (libsource (lib "eagle-import") (part "R-US_R0603"))
    )
    (comp (ref "R107")
      (value "10")
      (footprint "eagle-import:R0603")
      (libsource (lib "eagle-import") (part "R-US_R0603"))
    )
    (comp (ref "R108")
      (value "4.7k")
      (footprint "eagle-import:R0603")
      (libsource (lib "eagle-import") (part "R-US_R0603"))
    )
    (comp (ref "R109")
      (value "4.7k")
      (footprint "eagle-import:R0603")
      (libsource (lib "eagle-import") (part "R-US_R0603"))
    )
    (comp (ref "R110")
      (value "120")
      (footprint "eagle-import:R0603")
      (libsource (lib "eagle-import") (part "R-US_R0603"))
    )
    (comp (ref "R111")
      (value "10")
      (footprint "eagle-import:R0603")
      (libsource (lib "eagle-import") (part "R-US_R0603"))
    )
    (comp (ref "R112")
      (value "10")
      (footprint "eagle-import:R0603")
      (libsource (lib "eagle-import") (part "R-US_R0603"))
    )
    (comp (ref "R113")
      (value "4.7k")
      (footprint "eagle-import:R0603")
      (libsource (lib "eagle-import") (part "R-US_R0603"))
    )
    (comp (ref "R114")
      (value "4.7k")
      (footprint "eagle-import:R0603")
      (libsource (lib "eagle-import") (part "R-US_R0603"))
    )
    (comp (ref "R115")
      (value "120")
      (footprint "eagle-import:R0603")
      (libsource (lib "eagle-import") (part "R-US_R0603"))
    )
    (comp (ref "R116")
      (value "10")
      (footprint "eagle-import:R0603")
      (libsource (lib "eagle-import") (part "R-US_R0603"))
    )
    (comp (ref "R117")
      (value "10")
      (footprint "eagle-import:R0603")
      (libsource (lib "eagle-import") (part "R-US_R0603"))
    )
    (comp (ref "R118")
      (value "4.7k")
      (footprint "eagle-import:R0603")
      (libsource (lib "eagle-import") (part "R-US_R0603"))
    )
    (comp (ref "R119")
      (value "4.7k")
      (footprint "eagle-import:R0603")
      (libsource (lib "eagle-import") (part "R-US_R0603"))
    )
    (comp (ref "R120")
      (value "120")
      (footprint "eagle-import:R0603")
      (libsource (lib "eagle-import") (part "R-US_R0603"))
    )
    (comp (ref "R121")
      (value "10")
      (footprint "eagle-import:R0603")
      (libsource (lib "eagle-import") (part "R-US_R0603"))
    )
    (comp (ref "R122")
      (value "10")
      (footprint "eagle-import:R0603")
      (libsource (lib "eagle-import") (part "R-US_R0603"))
    )
    (comp (ref "RC2")
      (value "470")
      (footprint "eagle-import:R0603")
      (libsource (lib "eagle-import") (part "R-US_R0603"))
    )
    (comp (ref "RC3")
      (value "10R")
      (footprint "eagle-import:R0603")
      (libsource (lib "eagle-import") (part "R-US_R0603"))
    )
    (comp (ref "RC5")
      (value "470")
      (footprint "eagle-import:R0603")
      (libsource (lib "eagle-import") (part "R-US_R0603"))
    )
    (comp (ref "RC6")
      (value "1k")
      (footprint "eagle-import:R0603")
      (libsource (lib "eagle-import") (part "R-US_R0603"))
    )
    (comp (ref "RC7")
      (value "470")
      (footprint "eagle-import:R0603")
      (libsource (lib "eagle-import") (part "R-US_R0603"))
    )
    (comp (ref "RC9")
      (value "1k")
      (footprint "eagle-import:R0603")
      (libsource (lib "eagle-import") (part "R-US_R0603"))
    )
    (comp (ref "RC10")
      (value "470")
      (footprint "eagle-import:R0603")
      (libsource (lib "eagle-import") (part "R-US_R0603"))
    )
    (comp (ref "RC11")
      (value "1k")
      (footprint "eagle-import:R0603")
      (libsource (lib "eagle-import") (part "R-US_R0603"))
    )
    (comp (ref "RC12")
      (value "470")
      (footprint "eagle-import:R0603")
      (libsource (lib "eagle-import") (part "R-US_R0603"))
    )
    (comp (ref "RC13")
      (value "1k")
      (footprint "eagle-import:R0603")
      (libsource (lib "eagle-import") (part "R-US_R0603"))
    )
    (comp (ref "RC14")
      (value "470")
      (footprint "eagle-import:R0603")
      (libsource (lib "eagle-import") (part "R-US_R0603"))
    )
    (comp (ref "RC15")
      (value "1k")
      (footprint "eagle-import:R0603")
      (libsource (lib "eagle-import") (part "R-US_R0603"))
    )
    (comp (ref "RC16")
      (value "470")
      (footprint "eagle-import:R0603")
      (libsource (lib "eagle-import") (part "R-US_R0603"))
    )
    (comp (ref "RC17")
      (value "1k")
      (footprint "eagle-import:R0603")
      (libsource (lib "eagle-import") (part "R-US_R0603"))
    )
    (comp (ref "RC18")
      (value "470")
      (footprint "eagle-import:R0603")
      (libsource (lib "eagle-import") (part "R-US_R0603"))
    )
    (comp (ref "RC19")
      (value "1k")
      (footprint "eagle-import:R0603")
      (libsource (lib "eagle-import") (part "R-US_R0603"))
    )
    (comp (ref "RC20")
      (value "470")
      (footprint "eagle-import:R0603")
      (libsource (lib "eagle-import") (part "R-US_R0603"))
    )
    (comp (ref "RC21")
      (value "1k")
      (footprint "eagle-import:R0603")
      (libsource (lib "eagle-import") (part "R-US_R0603"))
    )
    (comp (ref "RC22")
      (value "470")
      (footprint "eagle-import:R0603")
      (libsource (lib "eagle-import") (part "R-US_R0603"))
    )
    (comp (ref "RC23")
      (value "1k")
      (footprint "eagle-import:R0603")
      (libsource (lib "eagle-import") (part "R-US_R0603"))
    )
    (comp (ref "RC30")
      (value "1k")
      (footprint "eagle-import:R0603")
      (libsource (lib "eagle-import") (part "R-US_R0603"))
    )
    (comp (ref "RC31")
      (value "1k")
      (footprint "eagle-import:R0603")
      (libsource (lib "eagle-import") (part "R-US_R0603"))
    )
    (comp (ref "RC34")
      (value "1k")
      (footprint "eagle-import:R0603")
      (libsource (lib "eagle-import") (part "R-US_R0603"))
    )
    (comp (ref "RC35")
      (value "1k")
      (footprint "eagle-import:R0603")
      (libsource (lib "eagle-import") (part "R-US_R0603"))
    )
    (comp (ref "RC36")
      (value "1k")
      (footprint "eagle-import:R0603")
      (libsource (lib "eagle-import") (part "R-US_R0603"))
    )
    (comp (ref "RC37")
      (value "1k")
      (footprint "eagle-import:R0603")
      (libsource (lib "eagle-import") (part "R-US_R0603"))
    )
    (comp (ref "RC38")
      (value "1k")
      (footprint "eagle-import:R0603")
      (libsource (lib "eagle-import") (part "R-US_R0603"))
    )
    (comp (ref "RC39")
      (value "1k")
      (footprint "eagle-import:R0603")
      (libsource (lib "eagle-import") (part "R-US_R0603"))
    )
    (comp (ref "RC40")
      (value "1k")
      (footprint "eagle-import:R0603")
      (libsource (lib "eagle-import") (part "R-US_R0603"))
    )
    (comp (ref "RC41")
      (value "470")
      (footprint "eagle-import:R0603")
      (libsource (lib "eagle-import") (part "R-US_R0603"))
    )
    (comp (ref "RC42")
      (value "470")
      (footprint "eagle-import:R0603")
      (libsource (lib "eagle-import") (part "R-US_R0603"))
    )
    (comp (ref "RC43")
      (value "470")
      (footprint "eagle-import:R0603")
      (libsource (lib "eagle-import") (part "R-US_R0603"))
    )
    (comp (ref "RC44")
      (value "470")
      (footprint "eagle-import:R0603")
      (libsource (lib "eagle-import") (part "R-US_R0603"))
    )
    (comp (ref "RC45")
      (value "470")
      (footprint "eagle-import:R0603")
      (libsource (lib "eagle-import") (part "R-US_R0603"))
    )
    (comp (ref "RC46")
      (value "470")
      (footprint "eagle-import:R0603")
      (libsource (lib "eagle-import") (part "R-US_R0603"))
    )
    (comp (ref "RC47")
      (value "470")
      (footprint "eagle-import:R0603")
      (libsource (lib "eagle-import") (part "R-US_R0603"))
    )
    (comp (ref "RC48")
      (value "470")
      (footprint "eagle-import:R0603")
      (libsource (lib "eagle-import") (part "R-US_R0603"))
    )
    (comp (ref "RC49")
      (value "470")
      (footprint "eagle-import:R0603")
      (libsource (lib "eagle-import") (part "R-US_R0603"))
    )
    (comp (ref "RESET")
      (value "MPT2")
      (footprint "eagle-import:2POL254")
      (libsource (lib "eagle-import") (part "MPT2"))
    )
    (comp (ref "RFID-1")
      (value "MOLEX-105309-1104")
      (footprint "eagle-import:MOLEX-105309-1104")
      (libsource (lib "eagle-import") (part "MOLEX-105309-1104"))
    )
    (comp (ref "RFID-2")
      (value "MOLEX-105309-1104")
      (footprint "eagle-import:MOLEX-105309-1104")
      (libsource (lib "eagle-import") (part "MOLEX-105309-1104"))
    )
    (comp (ref "RFID-3")
      (value "MOLEX-105309-1104")
      (footprint "eagle-import:MOLEX-105309-1104")
      (libsource (lib "eagle-import") (part "MOLEX-105309-1104"))
    )
    (comp (ref "RFID-4")
      (value "MOLEX-105309-1104")
      (footprint "eagle-import:MOLEX-105309-1104")
      (libsource (lib "eagle-import") (part "MOLEX-105309-1104"))
    )
    (comp (ref "RFID-5")
      (value "MOLEX-105309-1104")
      (footprint "eagle-import:MOLEX-105309-1104")
      (libsource (lib "eagle-import") (part "MOLEX-105309-1104"))
    )
    (comp (ref "RFID-6")
      (value "MOLEX-105309-1104")
      (footprint "eagle-import:MOLEX-105309-1104")
      (libsource (lib "eagle-import") (part "MOLEX-105309-1104"))
    )
    (comp (ref "RFID-7")
      (value "MOLEX-105309-1104")
      (footprint "eagle-import:MOLEX-105309-1104")
      (libsource (lib "eagle-import") (part "MOLEX-105309-1104"))
    )
    (comp (ref "RFID-8")
      (value "MOLEX-105309-1104")
      (footprint "eagle-import:MOLEX-105309-1104")
      (libsource (lib "eagle-import") (part "MOLEX-105309-1104"))
    )
    (comp (ref "RGB")
      (value "22-23-2031")
      (footprint "eagle-import:22-23-2031")
      (fields (field (name "MF") "MOLEX"))
      (libsource (lib "eagle-import") (part "22-23-2031"))
    )
    (comp (ref "RPL")
      (value "1K")
      (footprint "eagle-import:0603-RES")
      (libsource (lib "eagle-import") (part "RESISTOR0603-RES"))
    )
    (comp (ref "RRST")
      (value "1k")
      (footprint "eagle-import:R0603")
      (libsource (lib "eagle-import") (part "R-US_R0603"))
    )
    (comp (ref "SPI")
      (value "22-23-2041")
      (footprint "eagle-import:22-23-2041")
      (fields (field (name "MF") "MOLEX"))
      (libsource (lib "eagle-import") (part "22-23-2041"))
    )
    (comp (ref "SPI-1")
      (value "22-23-2051")
      (footprint "eagle-import:22-23-2051")
      (fields (field (name "MF") "MOLEX"))
      (libsource (lib "eagle-import") (part "22-23-2051"))
    )
    (comp (ref "SPI-2")
      (value "22-23-2051")
      (footprint "eagle-import:22-23-2051")
      (fields (field (name "MF") "MOLEX"))
      (libsource (lib "eagle-import") (part "22-23-2051"))
    )
    (comp (ref "U$1")
      (value "DRAGINO_SHIELD")
      (footprint "eagle-import:DRAGINO_SHIELD")
      (libsource (lib "eagle-import") (part "DRAGINO_SHIELD"))
    )
    (comp (ref "U$2")
      (value "BUZZER")
      (footprint "eagle-import:BUZZER")
      (libsource (lib "eagle-import") (part "BUZZER"))
    )
    (comp (ref "U$3")
      (value "BUZZER")
      (footprint "eagle-import:BUZZER")
      (libsource (lib "eagle-import") (part "BUZZER"))
    )
    (comp (ref "U$4")
      (value "GG0402050R3C2P")
      (footprint "eagle-import:0402")
      (libsource (lib "eagle-import") (part "GG0402050R3C2P"))
    )
    (comp (ref "U$5")
      (value "43045-0624-0624_CONNECTOR_2X3")
      (footprint "eagle-import:43045-0624_CONNECTOR_2X3")
      (libsource (lib "eagle-import") (part "43045-0624-0624_CONNECTOR_2X3"))
    )
    (comp (ref "U$6")
      (value "43045-0624-0624_CONNECTOR_2X3")
      (footprint "eagle-import:43045-0624_CONNECTOR_2X3")
      (libsource (lib "eagle-import") (part "43045-0624-0624_CONNECTOR_2X3"))
    )
    (comp (ref "U$7")
      (value "43045-0624-0624_CONNECTOR_2X3")
      (footprint "eagle-import:43045-0624_CONNECTOR_2X3")
      (libsource (lib "eagle-import") (part "43045-0624-0624_CONNECTOR_2X3"))
    )
    (comp (ref "U$8")
      (value "43045-0624-0624_CONNECTOR_2X3")
      (footprint "eagle-import:43045-0624_CONNECTOR_2X3")
      (libsource (lib "eagle-import") (part "43045-0624-0624_CONNECTOR_2X3"))
    )
    (comp (ref "U$9")
      (value "43045-0624-0624_CONNECTOR_2X3")
      (footprint "eagle-import:43045-0624_CONNECTOR_2X3")
      (libsource (lib "eagle-import") (part "43045-0624-0624_CONNECTOR_2X3"))
    )
    (comp (ref "U$10")
      (value "43045-0624-0624_CONNECTOR_2X3")
      (footprint "eagle-import:43045-0624_CONNECTOR_2X3")
      (libsource (lib "eagle-import") (part "43045-0624-0624_CONNECTOR_2X3"))
    )
    (comp (ref "U$11")
      (value "43045-0624-0624_CONNECTOR_2X3")
      (footprint "eagle-import:43045-0624_CONNECTOR_2X3")
      (libsource (lib "eagle-import") (part "43045-0624-0624_CONNECTOR_2X3"))
    )
    (comp (ref "U$12")
      (value "43045-0624-0624_CONNECTOR_2X3")
      (footprint "eagle-import:43045-0624_CONNECTOR_2X3")
      (libsource (lib "eagle-import") (part "43045-0624-0624_CONNECTOR_2X3"))
    )
    (comp (ref "U$13")
      (value "43045-0624-0624_CONNECTOR_2X3")
      (footprint "eagle-import:43045-0624_CONNECTOR_2X3")
      (libsource (lib "eagle-import") (part "43045-0624-0624_CONNECTOR_2X3"))
    )
    (comp (ref "U$14")
      (value "GG0402050R3C2P")
      (footprint "eagle-import:0402")
      (libsource (lib "eagle-import") (part "GG0402050R3C2P"))
    )
    (comp (ref "U$15")
      (value "GG0402050R3C2P")
      (footprint "eagle-import:0402")
      (libsource (lib "eagle-import") (part "GG0402050R3C2P"))
    )
    (comp (ref "U$16")
      (value "GG0402050R3C2P")
      (footprint "eagle-import:0402")
      (libsource (lib "eagle-import") (part "GG0402050R3C2P"))
    )
    (comp (ref "U$17")
      (value "GG0402050R3C2P")
      (footprint "eagle-import:0402")
      (libsource (lib "eagle-import") (part "GG0402050R3C2P"))
    )
    (comp (ref "U$18")
      (value "GG0402050R3C2P")
      (footprint "eagle-import:0402")
      (libsource (lib "eagle-import") (part "GG0402050R3C2P"))
    )
    (comp (ref "U$19")
      (value "GG0402050R3C2P")
      (footprint "eagle-import:0402")
      (libsource (lib "eagle-import") (part "GG0402050R3C2P"))
    )
    (comp (ref "U$20")
      (value "GG0402050R3C2P")
      (footprint "eagle-import:0402")
      (libsource (lib "eagle-import") (part "GG0402050R3C2P"))
    )
    (comp (ref "U$21")
      (value "GG0402050R3C2P")
      (footprint "eagle-import:0402")
      (libsource (lib "eagle-import") (part "GG0402050R3C2P"))
    )
    (comp (ref "U$22")
      (value "GG0402050R3C2P")
      (footprint "eagle-import:0402")
      (libsource (lib "eagle-import") (part "GG0402050R3C2P"))
    )
    (comp (ref "U$23")
      (value "GG0402050R3C2P")
      (footprint "eagle-import:0402")
      (libsource (lib "eagle-import") (part "GG0402050R3C2P"))
    )
    (comp (ref "U$24")
      (value "GG0402050R3C2P")
      (footprint "eagle-import:0402")
      (libsource (lib "eagle-import") (part "GG0402050R3C2P"))
    )
    (comp (ref "U$25")
      (value "GG0402050R3C2P")
      (footprint "eagle-import:0402")
      (libsource (lib "eagle-import") (part "GG0402050R3C2P"))
    )
    (comp (ref "U$26")
      (value "GG0402050R3C2P")
      (footprint "eagle-import:0402")
      (libsource (lib "eagle-import") (part "GG0402050R3C2P"))
    )
    (comp (ref "U$27")
      (value "GG0402050R3C2P")
      (footprint "eagle-import:0402")
      (libsource (lib "eagle-import") (part "GG0402050R3C2P"))
    )
    (comp (ref "U$28")
      (value "GG0402050R3C2P")
      (footprint "eagle-import:0402")
      (libsource (lib "eagle-import") (part "GG0402050R3C2P"))
    )
    (comp (ref "U$29")
      (value "GG0402050R3C2P")
      (footprint "eagle-import:0402")
      (libsource (lib "eagle-import") (part "GG0402050R3C2P"))
    )
    (comp (ref "U$30")
      (value "GG0402050R3C2P")
      (footprint "eagle-import:0402")
      (libsource (lib "eagle-import") (part "GG0402050R3C2P"))
    )
    (comp (ref "U$31")
      (value "NUP1301SOT23")
      (footprint "eagle-import:SOT23")
      (libsource (lib "eagle-import") (part "NUP1301SOT23"))
    )
    (comp (ref "U$32")
      (value "NUP1301SOT23")
      (footprint "eagle-import:SOT23")
      (libsource (lib "eagle-import") (part "NUP1301SOT23"))
    )
    (comp (ref "U$33")
      (value "NUP1301SOT23")
      (footprint "eagle-import:SOT23")
      (libsource (lib "eagle-import") (part "NUP1301SOT23"))
    )
    (comp (ref "U$34")
      (value "NUP1301SOT23")
      (footprint "eagle-import:SOT23")
      (libsource (lib "eagle-import") (part "NUP1301SOT23"))
    )
    (comp (ref "U$35")
      (value "NUP1301SOT23")
      (footprint "eagle-import:SOT23")
      (libsource (lib "eagle-import") (part "NUP1301SOT23"))
    )
    (comp (ref "U$36")
      (value "NUP1301SOT23")
      (footprint "eagle-import:SOT23")
      (libsource (lib "eagle-import") (part "NUP1301SOT23"))
    )
    (comp (ref "U$37")
      (value "MAX14571")
      (footprint "eagle-import:TSSOP14")
      (libsource (lib "eagle-import") (part "MAX14571"))
    )
    (comp (ref "U$38")
      (value "STPS5L60S")
      (footprint "eagle-import:SMC")
      (libsource (lib "eagle-import") (part "STPS5L60S"))
    )
    (comp (ref "U$39")
      (value "SM6T36CA")
      (footprint "eagle-import:DO214AA")
      (libsource (lib "eagle-import") (part "SM6T36CA"))
    )
    (comp (ref "U$40")
      (value "NC7WZ07P6X")
      (footprint "eagle-import:SC70-6L")
      (libsource (lib "eagle-import") (part "NC7WZ07P6X"))
    )
    (comp (ref "U$41")
      (value "EEV-FK1H331Q")
      (footprint "eagle-import:EEVFK1H331Q")
      (libsource (lib "eagle-import") (part "EEV-FK1H331Q"))
    )
    (comp (ref "U$42")
      (value "EEV-FK1H331Q")
      (footprint "eagle-import:EEVFK1H331Q")
      (libsource (lib "eagle-import") (part "EEV-FK1H331Q"))
    )
    (comp (ref "U$43")
      (value "EEV-FK1H331Q")
      (footprint "eagle-import:EEVFK1H331Q")
      (libsource (lib "eagle-import") (part "EEV-FK1H331Q"))
    )
    (comp (ref "U$44")
      (value "EEV-FK1H331Q")
      (footprint "eagle-import:EEVFK1H331Q")
      (libsource (lib "eagle-import") (part "EEV-FK1H331Q"))
    )
    (comp (ref "U$53")
      (value "MOLEX-105309-1104")
      (footprint "eagle-import:MOLEX-105309-1104")
      (libsource (lib "eagle-import") (part "MOLEX-105309-1104"))
    )
    (comp (ref "U2")
      (value "SN65HVD09DGGR")
      (footprint "eagle-import:SOP50P810X120-56N")
      (fields (field (name "DIGI-KEY_PART_NUMBER") "296-24051-1-ND") (field (name "MF") "Texas Instruments"))
      (libsource (lib "eagle-import") (part "SN65HVD09DGGR"))
    )
    (comp (ref "Y1")
      (value "RESONATORMU")
      (footprint "eagle-import:RESONATOR")
      (libsource (lib "eagle-import") (part "RESONATORMU"))
    )
    (comp (ref "Z1")
      (value "ZXTN2010Z")
      (footprint "eagle-import:SOT89")
      (libsource (lib "eagle-import") (part "NPN-TRANSISTIOR-2COLSOT89"))
    )
    (comp (ref "Z2")
      (value "ZXTN2010Z")
      (footprint "eagle-import:SOT89")
      (libsource (lib "eagle-import") (part "NPN-TRANSISTIOR-2COLSOT89"))
    )
    (comp (ref "Z3")
      (value "ZXTN2010Z")
      (footprint "eagle-import:SOT89")
      (libsource (lib "eagle-import") (part "NPN-TRANSISTIOR-2COLSOT89"))
    )
    (comp (ref "Z4")
      (value "ZXTN2010Z")
      (footprint "eagle-import:SOT89")
      (libsource (lib "eagle-import") (part "NPN-TRANSISTIOR-2COLSOT89"))
    )
    (comp (ref "Z5")
      (value "ZXTN2010Z")
      (footprint "eagle-import:SOT89")
      (libsource (lib "eagle-import") (part "NPN-TRANSISTIOR-2COLSOT89"))
    )
    (comp (ref "Z6")
      (value "ZXTN2010Z")
      (footprint "eagle-import:SOT89")
      (libsource (lib "eagle-import") (part "NPN-TRANSISTIOR-2COLSOT89"))
    )
    (comp (ref "Z7")
      (value "ZXTN2010Z")
      (footprint "eagle-import:SOT89")
      (libsource (lib "eagle-import") (part "NPN-TRANSISTIOR-2COLSOT89"))
    )
    (comp (ref "Z8")
      (value "ZXTN2010Z")
      (footprint "eagle-import:SOT89")
      (libsource (lib "eagle-import") (part "NPN-TRANSISTIOR-2COLSOT89"))
    )
    (comp (ref "Z9")
      (value "ZXTN2010Z")
      (footprint "eagle-import:SOT89")
      (libsource (lib "eagle-import") (part "NPN-TRANSISTIOR-2COLSOT89"))
    )
  )
  (nets
    (net (code "1") (name "+5V") (class "Default")
      (node (ref "+5V_SUPPLY") (pin "1") (pinfunction "1_1") (pintype "passive"))
      (node (ref "C11") (pin "1") (pinfunction "1_1") (pintype "passive"))
      (node (ref "C12") (pin "1") (pinfunction "1_1") (pintype "passive"))
      (node (ref "C13") (pin "1") (pinfunction "1_1") (pintype "passive"))
      (node (ref "C19") (pin "1") (pinfunction "1_1") (pintype "passive"))
      (node (ref "C4") (pin "1") (pinfunction "1_1") (pintype "passive"))
      (node (ref "D1") (pin "C") (pinfunction "C_C") (pintype "passive"))
      (node (ref "D3") (pin "C") (pinfunction "-_C") (pintype "passive"))
      (node (ref "I2C-1") (pin "1") (pinfunction "S_1") (pintype "passive"))
      (node (ref "I2C-2") (pin "1") (pinfunction "S_1") (pintype "passive"))
      (node (ref "IC1") (pin "3") (pinfunction "+5V_3") (pintype "power_in"))
      (node (ref "IC12") (pin "10") (pinfunction "VCC_10") (pintype "power_in"))
      (node (ref "IC12") (pin "100") (pinfunction "AVCC_100") (pintype "power_in"))
      (node (ref "IC12") (pin "31") (pinfunction "VCC1_31") (pintype "power_in"))
      (node (ref "IC12") (pin "61") (pinfunction "VCC2_61") (pintype "power_in"))
      (node (ref "IC12") (pin "80") (pinfunction "VCC3_80") (pintype "power_in"))
      (node (ref "OC3") (pin "14") (pinfunction "COL_14") (pintype "passive"))
      (node (ref "PC4") (pin "+") (pinfunction "+_+") (pintype "passive"))
      (node (ref "R1") (pin "1") (pinfunction "1_1") (pintype "passive"))
      (node (ref "R103") (pin "2") (pinfunction "2_2") (pintype "passive"))
      (node (ref "R108") (pin "2") (pinfunction "2_2") (pintype "passive"))
      (node (ref "R113") (pin "2") (pinfunction "2_2") (pintype "passive"))
      (node (ref "R118") (pin "2") (pinfunction "2_2") (pintype "passive"))
      (node (ref "R15") (pin "2") (pinfunction "2_2") (pintype "passive"))
      (node (ref "R15_BYPASS8") (pin "1") (pinfunction "1_1") (pintype "passive"))
      (node (ref "R18") (pin "2") (pinfunction "2_2") (pintype "passive"))
      (node (ref "R19") (pin "2") (pinfunction "2_2") (pintype "passive"))
      (node (ref "R2") (pin "1") (pinfunction "1_1") (pintype "passive"))
      (node (ref "R28") (pin "2") (pinfunction "2_2") (pintype "passive"))
      (node (ref "R35") (pin "1") (pinfunction "1_1") (pintype "passive"))
      (node (ref "R6") (pin "2") (pinfunction "2_2") (pintype "passive"))
      (node (ref "R83") (pin "2") (pinfunction "2_2") (pintype "passive"))
      (node (ref "R88") (pin "2") (pinfunction "2_2") (pintype "passive"))
      (node (ref "R93") (pin "2") (pinfunction "2_2") (pintype "passive"))
      (node (ref "R98") (pin "2") (pinfunction "2_2") (pintype "passive"))
      (node (ref "RC10") (pin "2") (pinfunction "2_2") (pintype "passive"))
      (node (ref "RC12") (pin "2") (pinfunction "2_2") (pintype "passive"))
      (node (ref "RC14") (pin "2") (pinfunction "2_2") (pintype "passive"))
      (node (ref "RC16") (pin "2") (pinfunction "2_2") (pintype "passive"))
      (node (ref "RC18") (pin "2") (pinfunction "2_2") (pintype "passive"))
      (node (ref "RC2") (pin "2") (pinfunction "2_2") (pintype "passive"))
      (node (ref "RC20") (pin "2") (pinfunction "2_2") (pintype "passive"))
      (node (ref "RC22") (pin "2") (pinfunction "2_2") (pintype "passive"))
      (node (ref "RC30") (pin "2") (pinfunction "2_2") (pintype "passive"))
      (node (ref "RC31") (pin "2") (pinfunction "2_2") (pintype "passive"))
      (node (ref "RC34") (pin "2") (pinfunction "2_2") (pintype "passive"))
      (node (ref "RC35") (pin "2") (pinfunction "2_2") (pintype "passive"))
      (node (ref "RC36") (pin "2") (pinfunction "2_2") (pintype "passive"))
      (node (ref "RC37") (pin "2") (pinfunction "2_2") (pintype "passive"))
      (node (ref "RC38") (pin "2") (pinfunction "2_2") (pintype "passive"))
      (node (ref "RC39") (pin "2") (pinfunction "2_2") (pintype "passive"))
      (node (ref "RC40") (pin "2") (pinfunction "2_2") (pintype "passive"))
      (node (ref "RC41") (pin "2") (pinfunction "2_2") (pintype "passive"))
      (node (ref "RC42") (pin "2") (pinfunction "2_2") (pintype "passive"))
      (node (ref "RC43") (pin "2") (pinfunction "2_2") (pintype "passive"))
      (node (ref "RC44") (pin "2") (pinfunction "2_2") (pintype "passive"))
      (node (ref "RC45") (pin "2") (pinfunction "2_2") (pintype "passive"))
      (node (ref "RC46") (pin "2") (pinfunction "2_2") (pintype "passive"))
      (node (ref "RC47") (pin "2") (pinfunction "2_2") (pintype "passive"))
      (node (ref "RC48") (pin "2") (pinfunction "2_2") (pintype "passive"))
      (node (ref "RC49") (pin "2") (pinfunction "2_2") (pintype "passive"))
      (node (ref "RC5") (pin "2") (pinfunction "2_2") (pintype "passive"))
      (node (ref "RC7") (pin "2") (pinfunction "2_2") (pintype "passive"))
      (node (ref "RFID-1") (pin "P$2") (pinfunction "P$2_P$2") (pintype "bidirectional"))
      (node (ref "RFID-2") (pin "P$2") (pinfunction "P$2_P$2") (pintype "bidirectional"))
      (node (ref "RFID-3") (pin "P$2") (pinfunction "P$2_P$2") (pintype "bidirectional"))
      (node (ref "RFID-4") (pin "P$2") (pinfunction "P$2_P$2") (pintype "bidirectional"))
      (node (ref "RFID-5") (pin "P$2") (pinfunction "P$2_P$2") (pintype "bidirectional"))
      (node (ref "RFID-6") (pin "P$2") (pinfunction "P$2_P$2") (pintype "bidirectional"))
      (node (ref "RFID-7") (pin "P$2") (pinfunction "P$2_P$2") (pintype "bidirectional"))
      (node (ref "RFID-8") (pin "P$2") (pinfunction "P$2_P$2") (pintype "bidirectional"))
      (node (ref "RGB") (pin "1") (pinfunction "S_1") (pintype "passive"))
      (node (ref "RPL") (pin "2") (pinfunction "2_2") (pintype "passive"))
      (node (ref "RRST") (pin "2") (pinfunction "2_2") (pintype "passive"))
      (node (ref "SPI-1") (pin "1") (pinfunction "S_1") (pintype "passive"))
      (node (ref "SPI-2") (pin "1") (pinfunction "S_1") (pintype "passive"))
      (node (ref "U$1") (pin "+5V") (pinfunction "+5V_+5V") (pintype "bidirectional"))
      (node (ref "U$1") (pin "5V") (pinfunction "5V_5V") (pintype "bidirectional"))
      (node (ref "U$2") (pin "P$1") (pinfunction "P$1_P$1") (pintype "bidirectional"))
      (node (ref "U$3") (pin "P$1") (pinfunction "P$1_P$1") (pintype "bidirectional"))
      (node (ref "U$31") (pin "2") (pinfunction "A2_2") (pintype "passive"))
      (node (ref "U$32") (pin "2") (pinfunction "A2_2") (pintype "passive"))
      (node (ref "U$33") (pin "2") (pinfunction "A2_2") (pintype "passive"))
      (node (ref "U$34") (pin "2") (pinfunction "A2_2") (pintype "passive"))
      (node (ref "U$35") (pin "2") (pinfunction "A2_2") (pintype "passive"))
      (node (ref "U$36") (pin "2") (pinfunction "A2_2") (pintype "passive"))
      (node (ref "U$37") (pin "EN") (pinfunction "EN_EN") (pintype "bidirectional"))
      (node (ref "U$37") (pin "RIEN") (pinfunction "RIEN_RIEN") (pintype "bidirectional"))
      (node (ref "U$40") (pin "4") (pinfunction "VCC_4") (pintype "bidirectional"))
      (node (ref "U$53") (pin "P$2") (pinfunction "P$2_P$2") (pintype "bidirectional"))
      (node (ref "U2") (pin "12") (pinfunction "VCC_2_12") (pintype "power_in"))
      (node (ref "U2") (pin "18") (pinfunction "VCC_3_18") (pintype "power_in"))
      (node (ref "U2") (pin "39") (pinfunction "VCC_4_39") (pintype "power_in"))
      (node (ref "U2") (pin "45") (pinfunction "VCC_45") (pintype "power_in"))
    )
    (net (code "2") (name "12PWR+") (class "Default")
      (node (ref "C3") (pin "1") (pinfunction "1_1") (pintype "passive"))
      (node (ref "IC1") (pin "1") (pinfunction "IN_1") (pintype "power_in"))
      (node (ref "OC1") (pin "10") (pinfunction "COL_10") (pintype "passive"))
      (node (ref "OC1") (pin "12") (pinfunction "COL_12") (pintype "passive"))
      (node (ref "OC1") (pin "14") (pinfunction "COL_14") (pintype "passive"))
      (node (ref "OC1") (pin "16") (pinfunction "COL_16") (pintype "passive"))
      (node (ref "OC2") (pin "10") (pinfunction "COL_10") (pintype "passive"))
      (node (ref "OC2") (pin "12") (pinfunction "COL_12") (pintype "passive"))
      (node (ref "OC2") (pin "14") (pinfunction "COL_14") (pintype "passive"))
      (node (ref "OC2") (pin "16") (pinfunction "COL_16") (pintype "passive"))
      (node (ref "OC4") (pin "16") (pinfunction "COL_16") (pintype "passive"))
      (node (ref "U$10") (pin "2") (pinfunction "2_2") (pintype "bidirectional"))
      (node (ref "U$11") (pin "2") (pinfunction "2_2") (pintype "bidirectional"))
      (node (ref "U$12") (pin "2") (pinfunction "2_2") (pintype "bidirectional"))
      (node (ref "U$13") (pin "2") (pinfunction "2_2") (pintype "bidirectional"))
      (node (ref "U$37") (pin "OUT@1") (pinfunction "OUT_OUT@1") (pintype "bidirectional"))
      (node (ref "U$37") (pin "OUT@2") (pinfunction "OUT_OUT@2") (pintype "bidirectional"))
      (node (ref "U$37") (pin "OUT@3") (pinfunction "OUT_OUT@3") (pintype "bidirectional"))
      (node (ref "U$38") (pin "1") (pinfunction "P$2_1") (pintype "bidirectional"))
      (node (ref "U$41") (pin "P$2") (pinfunction "P$1_P$2") (pintype "bidirectional"))
      (node (ref "U$42") (pin "P$2") (pinfunction "P$1_P$2") (pintype "bidirectional"))
      (node (ref "U$43") (pin "P$2") (pinfunction "P$1_P$2") (pintype "bidirectional"))
      (node (ref "U$44") (pin "P$2") (pinfunction "P$1_P$2") (pintype "bidirectional"))
      (node (ref "U$5") (pin "2") (pinfunction "2_2") (pintype "bidirectional"))
      (node (ref "U$6") (pin "2") (pinfunction "2_2") (pintype "bidirectional"))
      (node (ref "U$7") (pin "2") (pinfunction "2_2") (pintype "bidirectional"))
      (node (ref "U$8") (pin "2") (pinfunction "2_2") (pintype "bidirectional"))
      (node (ref "U$9") (pin "2") (pinfunction "2_2") (pintype "bidirectional"))
      (node (ref "Z1") (pin "2") (pinfunction "C_2") (pintype "passive"))
      (node (ref "Z2") (pin "2") (pinfunction "C_2") (pintype "passive"))
      (node (ref "Z3") (pin "2") (pinfunction "C_2") (pintype "passive"))
      (node (ref "Z4") (pin "2") (pinfunction "C_2") (pintype "passive"))
      (node (ref "Z5") (pin "2") (pinfunction "C_2") (pintype "passive"))
      (node (ref "Z6") (pin "2") (pinfunction "C_2") (pintype "passive"))
      (node (ref "Z7") (pin "2") (pinfunction "C_2") (pintype "passive"))
      (node (ref "Z8") (pin "2") (pinfunction "C_2") (pintype "passive"))
      (node (ref "Z9") (pin "2") (pinfunction "C_2") (pintype "passive"))
    )
    (net (code "3") (name "12PWR-") (class "Default")
      (node (ref "C1") (pin "1") (pinfunction "1_1") (pintype "passive"))
      (node (ref "D2") (pin "C") (pinfunction "C_C") (pintype "passive"))
      (node (ref "PFET-1") (pin "3") (pinfunction "S_3") (pintype "passive"))
      (node (ref "R31") (pin "1") (pinfunction "1_1") (pintype "passive"))
      (node (ref "R32") (pin "1") (pinfunction "1_1") (pintype "passive"))
      (node (ref "U$37") (pin "IN@1") (pinfunction "IN_IN@1") (pintype "bidirectional"))
      (node (ref "U$37") (pin "IN@2") (pinfunction "IN_IN@2") (pintype "bidirectional"))
      (node (ref "U$37") (pin "IN@3") (pinfunction "IN_IN@3") (pintype "bidirectional"))
      (node (ref "U$39") (pin "C") (pinfunction "P$2_C") (pintype "bidirectional"))
    )
    (net (code "4") (name "12V_SUPPLY") (class "Default")
      (node (ref "12V_POWER_JACK") (pin "1") (pinfunction "1_1") (pintype "passive"))
      (node (ref "PFET-1") (pin "2") (pinfunction "D_2") (pintype "passive"))
      (node (ref "POWER") (pin "2") (pinfunction "KL_2") (pintype "passive"))
    )
    (net (code "5") (name "AREF") (class "Default")
      (node (ref "C6") (pin "1") (pinfunction "1_1") (pintype "passive"))
      (node (ref "IC12") (pin "98") (pinfunction "AREF_98") (pintype "bidirectional"))
      (node (ref "U$1") (pin "AREF") (pinfunction "AREF_AREF") (pintype "bidirectional"))
    )
    (net (code "6") (name "BSR") (class "Default")
      (node (ref "IC12") (pin "85") (pinfunction "PK4(ADC12/PCINT20)_85") (pintype "bidirectional"))
      (node (ref "U2") (pin "2") (pinfunction "BSR_2") (pintype "input"))
    )
    (net (code "7") (name "CDE0") (class "Default")
      (node (ref "IC12") (pin "88") (pinfunction "PK1(ADC9/PCINT17)_88") (pintype "bidirectional"))
      (node (ref "U2") (pin "54") (pinfunction "CDE0_54") (pintype "input"))
    )
    (net (code "8") (name "CDE1") (class "Default")
      (node (ref "IC12") (pin "87") (pinfunction "PK2(ADC10/PCINT18)_87") (pintype "bidirectional"))
      (node (ref "U2") (pin "55") (pinfunction "CDE1_55") (pintype "input"))
    )
    (net (code "9") (name "CDE2") (class "Default")
      (node (ref "IC12") (pin "86") (pinfunction "PK3(ADC11/PCINT19)_86") (pintype "bidirectional"))
      (node (ref "U2") (pin "56") (pinfunction "CDE2_56") (pintype "input"))
    )
    (net (code "10") (name "CS") (class "Default")
      (node (ref "IC12") (pin "19") (pinfunction "(SS/PCINT0)PB0_19") (pintype "bidirectional"))
      (node (ref "SPI") (pin "4") (pinfunction "S_4") (pintype "passive"))
      (node (ref "SPI-1") (pin "4") (pinfunction "S_4") (pintype "passive"))
      (node (ref "SPI-2") (pin "4") (pinfunction "S_4") (pintype "passive"))
      (node (ref "U$34") (pin "3") (pinfunction "K1K2_3") (pintype "passive"))
    )
    (net (code "11") (name "D3") (class "Default")
      (node (ref "IC12") (pin "7") (pinfunction "(OC3C/INT5)PE5_7") (pintype "bidirectional"))
    )
    (net (code "12") (name "D4_BUZZER") (class "Default")
      (node (ref "IC12") (pin "1") (pinfunction "(OC0B)PG5_1") (pintype "bidirectional"))
      (node (ref "OC3") (pin "4") (pinfunction "C_4") (pintype "passive"))
    )
    (net (code "13") (name "DE{slash}RE*-RFID1") (class "Default")
      (node (ref "IC12") (pin "97") (pinfunction "(ADC0)PF0_97") (pintype "bidirectional"))
    )
    (net (code "14") (name "DE{slash}RE*-RFID2") (class "Default")
      (node (ref "IC12") (pin "96") (pinfunction "(ADC1)PF1_96") (pintype "bidirectional"))
    )
    (net (code "15") (name "DE{slash}RE*-RFID3") (class "Default")
      (node (ref "IC12") (pin "95") (pinfunction "(ADC2)PF2_95") (pintype "bidirectional"))
    )
    (net (code "16") (name "DE{slash}RE*-RFID4") (class "Default")
      (node (ref "IC12") (pin "94") (pinfunction "(ADC3)PF3_94") (pintype "bidirectional"))
    )
    (net (code "17") (name "DE{slash}RE*-RFID5") (class "Default")
      (node (ref "IC12") (pin "93") (pinfunction "(ADC4/TCK)PF4_93") (pintype "bidirectional"))
    )
    (net (code "18") (name "DE{slash}RE*-RFID6") (class "Default")
      (node (ref "IC12") (pin "92") (pinfunction "(ADC5/TMS)PF5_92") (pintype "bidirectional"))
    )
    (net (code "19") (name "DE{slash}RE*-RFID7") (class "Default")
      (node (ref "IC12") (pin "91") (pinfunction "(ADC6/TDO)PF6_91") (pintype "bidirectional"))
    )
    (net (code "20") (name "DE{slash}RE*-RFID8") (class "Default")
      (node (ref "IC12") (pin "90") (pinfunction "(ADC7/TDI)PF7_90") (pintype "bidirectional"))
    )
    (net (code "21") (name "DE{slash}RE*-RFID9") (class "Default")
      (node (ref "IC12") (pin "89") (pinfunction "PK0(ADC8/PCINT16)_89") (pintype "bidirectional"))
    )
    (net (code "22") (name "GND") (class "Default")
      (node (ref "+5V_SUPPLY") (pin "2") (pinfunction "1_2") (pintype "passive"))
      (node (ref "12V_POWER_JACK") (pin "3") (pinfunction "3_3") (pintype "passive"))
      (node (ref "ADJUST_OVLO") (pin "2") (pinfunction "2_2") (pintype "passive"))
      (node (ref "ADJUST_UVLO") (pin "2") (pinfunction "2_2") (pintype "passive"))
      (node (ref "C1") (pin "2") (pinfunction "2_2") (pintype "passive"))
      (node (ref "C11") (pin "2") (pinfunction "2_2") (pintype "passive"))
      (node (ref "C12") (pin "2") (pinfunction "2_2") (pintype "passive"))
      (node (ref "C13") (pin "2") (pinfunction "2_2") (pintype "passive"))
      (node (ref "C15") (pin "2") (pinfunction "2_2") (pintype "passive"))
      (node (ref "C19") (pin "2") (pinfunction "2_2") (pintype "passive"))
      (node (ref "C2") (pin "2") (pinfunction "2_2") (pintype "passive"))
      (node (ref "C3") (pin "2") (pinfunction "2_2") (pintype "passive"))
      (node (ref "C4") (pin "2") (pinfunction "2_2") (pintype "passive"))
      (node (ref "C6") (pin "2") (pinfunction "2_2") (pintype "passive"))
      (node (ref "I2C-1") (pin "4") (pinfunction "S_4") (pintype "passive"))
      (node (ref "I2C-2") (pin "4") (pinfunction "S_4") (pintype "passive"))
      (node (ref "IC1") (pin "2") (pinfunction "GND_2") (pintype "power_in"))
      (node (ref "IC12") (pin "11") (pinfunction "GND_11") (pintype "power_in"))
      (node (ref "IC12") (pin "32") (pinfunction "GND1_32") (pintype "power_in"))
      (node (ref "IC12") (pin "62") (pinfunction "GND2_62") (pintype "power_in"))
      (node (ref "IC12") (pin "81") (pinfunction "GND3_81") (pintype "power_in"))
      (node (ref "IC12") (pin "99") (pinfunction "AGND_99") (pintype "power_in"))
      (node (ref "OC4") (pin "9") (pinfunction "EMIT_9") (pintype "passive"))
      (node (ref "OC5") (pin "11") (pinfunction "EMIT_11") (pintype "passive"))
      (node (ref "OC5") (pin "13") (pinfunction "EMIT_13") (pintype "passive"))
      (node (ref "OC5") (pin "15") (pinfunction "EMIT_15") (pintype "passive"))
      (node (ref "OC5") (pin "9") (pinfunction "EMIT_9") (pintype "passive"))
      (node (ref "OC6") (pin "11") (pinfunction "EMIT_11") (pintype "passive"))
      (node (ref "OC6") (pin "13") (pinfunction "EMIT_13") (pintype "passive"))
      (node (ref "OC6") (pin "15") (pinfunction "EMIT_15") (pintype "passive"))
      (node (ref "OC6") (pin "9") (pinfunction "EMIT_9") (pintype "passive"))
      (node (ref "PC4") (pin "-") (pinfunction "-_-") (pintype "passive"))
      (node (ref "POWER") (pin "1") (pinfunction "KL_1") (pintype "passive"))
      (node (ref "PWR-LED") (pin "C") (pinfunction "C_C") (pintype "passive"))
      (node (ref "R104") (pin "1") (pinfunction "1_1") (pintype "passive"))
      (node (ref "R109") (pin "1") (pinfunction "1_1") (pintype "passive"))
      (node (ref "R114") (pin "1") (pinfunction "1_1") (pintype "passive"))
      (node (ref "R119") (pin "1") (pinfunction "1_1") (pintype "passive"))
      (node (ref "R17") (pin "2") (pinfunction "2_2") (pintype "passive"))
      (node (ref "R18") (pin "1") (pinfunction "1_1") (pintype "passive"))
      (node (ref "R19") (pin "1") (pinfunction "1_1") (pintype "passive"))
      (node (ref "R20") (pin "2") (pinfunction "2_2") (pintype "passive"))
      (node (ref "R21") (pin "2") (pinfunction "2_2") (pintype "passive"))
      (node (ref "R22") (pin "2") (pinfunction "2_2") (pintype "passive"))
      (node (ref "R23") (pin "2") (pinfunction "2_2") (pintype "passive"))
      (node (ref "R24") (pin "2") (pinfunction "2_2") (pintype "passive"))
      (node (ref "R25") (pin "2") (pinfunction "2_2") (pintype "passive"))
      (node (ref "R26") (pin "2") (pinfunction "2_2") (pintype "passive"))
      (node (ref "R27") (pin "2") (pinfunction "2_2") (pintype "passive"))
      (node (ref "R29") (pin "1") (pinfunction "1_1") (pintype "passive"))
      (node (ref "R33") (pin "2") (pinfunction "2_2") (pintype "passive"))
      (node (ref "R69") (pin "2") (pinfunction "2_2") (pintype "passive"))
      (node (ref "R7") (pin "2") (pinfunction "2_2") (pintype "passive"))
      (node (ref "R84") (pin "1") (pinfunction "1_1") (pintype "passive"))
      (node (ref "R89") (pin "1") (pinfunction "1_1") (pintype "passive"))
      (node (ref "R94") (pin "1") (pinfunction "1_1") (pintype "passive"))
      (node (ref "R99") (pin "1") (pinfunction "1_1") (pintype "passive"))
      (node (ref "RC11") (pin "1") (pinfunction "1_1") (pintype "passive"))
      (node (ref "RC13") (pin "1") (pinfunction "1_1") (pintype "passive"))
      (node (ref "RC15") (pin "1") (pinfunction "1_1") (pintype "passive"))
      (node (ref "RC17") (pin "1") (pinfunction "1_1") (pintype "passive"))
      (node (ref "RC19") (pin "1") (pinfunction "1_1") (pintype "passive"))
      (node (ref "RC21") (pin "1") (pinfunction "1_1") (pintype "passive"))
      (node (ref "RC23") (pin "1") (pinfunction "1_1") (pintype "passive"))
      (node (ref "RC3") (pin "1") (pinfunction "1_1") (pintype "passive"))
      (node (ref "RC6") (pin "1") (pinfunction "1_1") (pintype "passive"))
      (node (ref "RC9") (pin "1") (pinfunction "1_1") (pintype "passive"))
      (node (ref "RESET") (pin "2") (pinfunction "1_2") (pintype "passive"))
      (node (ref "RFID-1") (pin "P$3") (pinfunction "P$3_P$3") (pintype "bidirectional"))
      (node (ref "RFID-2") (pin "P$3") (pinfunction "P$3_P$3") (pintype "bidirectional"))
      (node (ref "RFID-3") (pin "P$3") (pinfunction "P$3_P$3") (pintype "bidirectional"))
      (node (ref "RFID-4") (pin "P$3") (pinfunction "P$3_P$3") (pintype "bidirectional"))
      (node (ref "RFID-5") (pin "P$3") (pinfunction "P$3_P$3") (pintype "bidirectional"))
      (node (ref "RFID-6") (pin "P$3") (pinfunction "P$3_P$3") (pintype "bidirectional"))
      (node (ref "RFID-7") (pin "P$3") (pinfunction "P$3_P$3") (pintype "bidirectional"))
      (node (ref "RFID-8") (pin "P$3") (pinfunction "P$3_P$3") (pintype "bidirectional"))
      (node (ref "RGB") (pin "3") (pinfunction "S_3") (pintype "passive"))
      (node (ref "SPI-1") (pin "5") (pinfunction "S_5") (pintype "passive"))
      (node (ref "SPI-2") (pin "5") (pinfunction "S_5") (pintype "passive"))
      (node (ref "U$1") (pin "GND") (pinfunction "GND_GND") (pintype "bidirectional"))
      (node (ref "U$1") (pin "GND@1") (pinfunction "GND_GND@1") (pintype "bidirectional"))
      (node (ref "U$1") (pin "GND@2") (pinfunction "GND_GND@2") (pintype "bidirectional"))
      (node (ref "U$1") (pin "GND@3") (pinfunction "GND_GND@3") (pintype "bidirectional"))
      (node (ref "U$10") (pin "1") (pinfunction "1_1") (pintype "bidirectional"))
      (node (ref "U$10") (pin "4") (pinfunction "4_4") (pintype "bidirectional"))
      (node (ref "U$11") (pin "1") (pinfunction "1_1") (pintype "bidirectional"))
      (node (ref "U$11") (pin "4") (pinfunction "4_4") (pintype "bidirectional"))
      (node (ref "U$12") (pin "1") (pinfunction "1_1") (pintype "bidirectional"))
      (node (ref "U$12") (pin "4") (pinfunction "4_4") (pintype "bidirectional"))
      (node (ref "U$13") (pin "1") (pinfunction "1_1") (pintype "bidirectional"))
      (node (ref "U$13") (pin "4") (pinfunction "4_4") (pintype "bidirectional"))
      (node (ref "U$14") (pin "A") (pinfunction "1_A") (pintype "bidirectional"))
      (node (ref "U$15") (pin "A") (pinfunction "1_A") (pintype "bidirectional"))
      (node (ref "U$16") (pin "A") (pinfunction "1_A") (pintype "bidirectional"))
      (node (ref "U$17") (pin "A") (pinfunction "1_A") (pintype "bidirectional"))
      (node (ref "U$18") (pin "A") (pinfunction "1_A") (pintype "bidirectional"))
      (node (ref "U$19") (pin "A") (pinfunction "1_A") (pintype "bidirectional"))
      (node (ref "U$20") (pin "A") (pinfunction "1_A") (pintype "bidirectional"))
      (node (ref "U$21") (pin "A") (pinfunction "1_A") (pintype "bidirectional"))
      (node (ref "U$22") (pin "A") (pinfunction "1_A") (pintype "bidirectional"))
      (node (ref "U$23") (pin "A") (pinfunction "1_A") (pintype "bidirectional"))
      (node (ref "U$24") (pin "A") (pinfunction "1_A") (pintype "bidirectional"))
      (node (ref "U$25") (pin "A") (pinfunction "1_A") (pintype "bidirectional"))
      (node (ref "U$26") (pin "A") (pinfunction "1_A") (pintype "bidirectional"))
      (node (ref "U$27") (pin "A") (pinfunction "1_A") (pintype "bidirectional"))
      (node (ref "U$28") (pin "A") (pinfunction "1_A") (pintype "bidirectional"))
      (node (ref "U$29") (pin "A") (pinfunction "1_A") (pintype "bidirectional"))
      (node (ref "U$30") (pin "A") (pinfunction "1_A") (pintype "bidirectional"))
      (node (ref "U$31") (pin "1") (pinfunction "A1_1") (pintype "passive"))
      (node (ref "U$32") (pin "1") (pinfunction "A1_1") (pintype "passive"))
      (node (ref "U$33") (pin "1") (pinfunction "A1_1") (pintype "passive"))
      (node (ref "U$34") (pin "1") (pinfunction "A1_1") (pintype "passive"))
      (node (ref "U$35") (pin "1") (pinfunction "A1_1") (pintype "passive"))
      (node (ref "U$36") (pin "1") (pinfunction "A1_1") (pintype "passive"))
      (node (ref "U$37") (pin "GND") (pinfunction "GND_GND") (pintype "bidirectional"))
      (node (ref "U$37") (pin "HVEN") (pinfunction "HVEN_HVEN") (pintype "bidirectional"))
      (node (ref "U$38") (pin "2") (pinfunction "P$1_2") (pintype "bidirectional"))
      (node (ref "U$39") (pin "A") (pinfunction "P$1_A") (pintype "bidirectional"))
      (node (ref "U$4") (pin "A") (pinfunction "1_A") (pintype "bidirectional"))
      (node (ref "U$40") (pin "3") (pinfunction "GND_3") (pintype "bidirectional"))
      (node (ref "U$41") (pin "P$1") (pinfunction "P$2_P$1") (pintype "bidirectional"))
      (node (ref "U$42") (pin "P$1") (pinfunction "P$2_P$1") (pintype "bidirectional"))
      (node (ref "U$43") (pin "P$1") (pinfunction "P$2_P$1") (pintype "bidirectional"))
      (node (ref "U$44") (pin "P$1") (pinfunction "P$2_P$1") (pintype "bidirectional"))
      (node (ref "U$5") (pin "1") (pinfunction "1_1") (pintype "bidirectional"))
      (node (ref "U$5") (pin "4") (pinfunction "4_4") (pintype "bidirectional"))
      (node (ref "U$53") (pin "P$3") (pinfunction "P$3_P$3") (pintype "bidirectional"))
      (node (ref "U$6") (pin "1") (pinfunction "1_1") (pintype "bidirectional"))
      (node (ref "U$6") (pin "4") (pinfunction "4_4") (pintype "bidirectional"))
      (node (ref "U$7") (pin "1") (pinfunction "1_1") (pintype "bidirectional"))
      (node (ref "U$7") (pin "4") (pinfunction "4_4") (pintype "bidirectional"))
      (node (ref "U$8") (pin "1") (pinfunction "1_1") (pintype "bidirectional"))
      (node (ref "U$8") (pin "4") (pinfunction "4_4") (pintype "bidirectional"))
      (node (ref "U$9") (pin "1") (pinfunction "1_1") (pintype "bidirectional"))
      (node (ref "U$9") (pin "4") (pinfunction "4_4") (pintype "bidirectional"))
      (node (ref "U2") (pin "1") (pinfunction "GND_2_1") (pintype "passive"))
      (node (ref "U2") (pin "13") (pinfunction "GND_3_13") (pintype "passive"))
      (node (ref "U2") (pin "14") (pinfunction "GND_4_14") (pintype "passive"))
      (node (ref "U2") (pin "15") (pinfunction "GND_5_15") (pintype "passive"))
      (node (ref "U2") (pin "16") (pinfunction "GND_6_16") (pintype "passive"))
      (node (ref "U2") (pin "17") (pinfunction "GND_7_17") (pintype "passive"))
      (node (ref "U2") (pin "40") (pinfunction "GND_8_40") (pintype "passive"))
      (node (ref "U2") (pin "41") (pinfunction "GND_9_41") (pintype "passive"))
      (node (ref "U2") (pin "42") (pinfunction "GND_10_42") (pintype "passive"))
      (node (ref "U2") (pin "43") (pinfunction "GND_11_43") (pintype "passive"))
      (node (ref "U2") (pin "44") (pinfunction "GND_44") (pintype "passive"))
      (node (ref "Y1") (pin "2") (pinfunction "2_2") (pintype "passive"))
    )
    (net (code "23") (name "GRE*") (class "Default")
      (node (ref "IC12") (pin "84") (pinfunction "PK5(ADC13/PCINT21)_84") (pintype "bidirectional"))
      (node (ref "U2") (pin "3") (pinfunction "~{GRE}_3") (pintype "input"))
    )
    (net (code "24") (name "MISO") (class "Default")
      (node (ref "IC12") (pin "22") (pinfunction "(MISO/PCINT3)PB3_22") (pintype "bidirectional"))
      (node (ref "SPI") (pin "2") (pinfunction "S_2") (pintype "passive"))
      (node (ref "SPI-2") (pin "2") (pinfunction "S_2") (pintype "passive"))
      (node (ref "U$1") (pin "MISO") (pinfunction "MISO_MISO") (pintype "bidirectional"))
      (node (ref "U$32") (pin "3") (pinfunction "K1K2_3") (pintype "passive"))
    )
    (net (code "25") (name "MOSI") (class "Default")
      (node (ref "IC12") (pin "21") (pinfunction "(MOSI/PCINT2)PB2_21") (pintype "bidirectional"))
      (node (ref "SPI") (pin "1") (pinfunction "S_1") (pintype "passive"))
      (node (ref "SPI-1") (pin "2") (pinfunction "S_2") (pintype "passive"))
      (node (ref "U$1") (pin "MOSI") (pinfunction "MOSI_MOSI") (pintype "bidirectional"))
      (node (ref "U$31") (pin "3") (pinfunction "K1K2_3") (pintype "passive"))
    )
    (net (code "26") (name "Net-(D3-+)") (class "Default")
      (node (ref "D3") (pin "A") (pinfunction "+_A") (pintype "passive"))
      (node (ref "Q3") (pin "3") (pinfunction "C_3") (pintype "passive"))
      (node (ref "U$2") (pin "P$2") (pinfunction "P$2_P$2") (pintype "bidirectional"))
      (node (ref "U$3") (pin "P$2") (pinfunction "P$2_P$2") (pintype "bidirectional"))
    )
    (net (code "27") (name "Net-(OC1A-A)") (class "Default")
      (node (ref "OC1") (pin "1") (pinfunction "A_1") (pintype "passive"))
      (node (ref "RC5") (pin "1") (pinfunction "1_1") (pintype "passive"))
    )
    (net (code "28") (name "Net-(OC1A-EMIT)") (class "Default")
      (node (ref "OC1") (pin "15") (pinfunction "EMIT_15") (pintype "passive"))
      (node (ref "R3") (pin "2") (pinfunction "2_2") (pintype "passive"))
    )
    (net (code "29") (name "Net-(OC1B-A)") (class "Default")
      (node (ref "OC1") (pin "3") (pinfunction "A_3") (pintype "passive"))
      (node (ref "RC7") (pin "1") (pinfunction "1_1") (pintype "passive"))
    )
    (net (code "30") (name "Net-(OC1B-EMIT)") (class "Default")
      (node (ref "OC1") (pin "13") (pinfunction "EMIT_13") (pintype "passive"))
      (node (ref "R4") (pin "2") (pinfunction "2_2") (pintype "passive"))
    )
    (net (code "31") (name "Net-(OC1C-A)") (class "Default")
      (node (ref "OC1") (pin "5") (pinfunction "A_5") (pintype "passive"))
      (node (ref "RC10") (pin "1") (pinfunction "1_1") (pintype "passive"))
    )
    (net (code "32") (name "Net-(OC1C-EMIT)") (class "Default")
      (node (ref "OC1") (pin "11") (pinfunction "EMIT_11") (pintype "passive"))
      (node (ref "R8") (pin "2") (pinfunction "2_2") (pintype "passive"))
    )
    (net (code "33") (name "Net-(OC1D-A)") (class "Default")
      (node (ref "OC1") (pin "7") (pinfunction "A_7") (pintype "passive"))
      (node (ref "RC12") (pin "1") (pinfunction "1_1") (pintype "passive"))
    )
    (net (code "34") (name "Net-(OC1D-EMIT)") (class "Default")
      (node (ref "OC1") (pin "9") (pinfunction "EMIT_9") (pintype "passive"))
      (node (ref "R9") (pin "2") (pinfunction "2_2") (pintype "passive"))
    )
    (net (code "35") (name "Net-(OC2A-A)") (class "Default")
      (node (ref "OC2") (pin "1") (pinfunction "A_1") (pintype "passive"))
      (node (ref "RC14") (pin "1") (pinfunction "1_1") (pintype "passive"))
    )
    (net (code "36") (name "Net-(OC2A-EMIT)") (class "Default")
      (node (ref "OC2") (pin "15") (pinfunction "EMIT_15") (pintype "passive"))
      (node (ref "R10") (pin "2") (pinfunction "2_2") (pintype "passive"))
    )
    (net (code "37") (name "Net-(OC2B-A)") (class "Default")
      (node (ref "OC2") (pin "3") (pinfunction "A_3") (pintype "passive"))
      (node (ref "RC16") (pin "1") (pinfunction "1_1") (pintype "passive"))
    )
    (net (code "38") (name "Net-(OC2B-EMIT)") (class "Default")
      (node (ref "OC2") (pin "13") (pinfunction "EMIT_13") (pintype "passive"))
      (node (ref "R11") (pin "2") (pinfunction "2_2") (pintype "passive"))
    )
    (net (code "39") (name "Net-(OC2C-A)") (class "Default")
      (node (ref "OC2") (pin "5") (pinfunction "A_5") (pintype "passive"))
      (node (ref "RC18") (pin "1") (pinfunction "1_1") (pintype "passive"))
    )
    (net (code "40") (name "Net-(OC2C-EMIT)") (class "Default")
      (node (ref "OC2") (pin "11") (pinfunction "EMIT_11") (pintype "passive"))
      (node (ref "R12") (pin "2") (pinfunction "2_2") (pintype "passive"))
    )
    (net (code "41") (name "Net-(OC2D-A)") (class "Default")
      (node (ref "OC2") (pin "7") (pinfunction "A_7") (pintype "passive"))
      (node (ref "RC20") (pin "1") (pinfunction "1_1") (pintype "passive"))
    )
    (net (code "42") (name "Net-(OC2D-EMIT)") (class "Default")
      (node (ref "OC2") (pin "9") (pinfunction "EMIT_9") (pintype "passive"))
      (node (ref "R13") (pin "2") (pinfunction "2_2") (pintype "passive"))
    )
    (net (code "43") (name "Net-(OC3B-A)") (class "Default")
      (node (ref "OC3") (pin "3") (pinfunction "A_3") (pintype "passive"))
      (node (ref "RC2") (pin "1") (pinfunction "1_1") (pintype "passive"))
    )
    (net (code "44") (name "Net-(OC3B-EMIT)") (class "Default")
      (node (ref "OC3") (pin "13") (pinfunction "EMIT_13") (pintype "passive"))
      (node (ref "R16") (pin "2") (pinfunction "2_2") (pintype "passive"))
    )
    (net (code "45") (name "Net-(OC4A-A)") (class "Default")
      (node (ref "OC4") (pin "1") (pinfunction "A_1") (pintype "passive"))
      (node (ref "RC22") (pin "1") (pinfunction "1_1") (pintype "passive"))
    )
    (net (code "46") (name "Net-(OC4A-EMIT)") (class "Default")
      (node (ref "OC4") (pin "15") (pinfunction "EMIT_15") (pintype "passive"))
      (node (ref "R14") (pin "2") (pinfunction "2_2") (pintype "passive"))
    )
    (net (code "47") (name "Net-(OC4D-A)") (class "Default")
      (node (ref "OC4") (pin "7") (pinfunction "A_7") (pintype "passive"))
      (node (ref "RC48") (pin "1") (pinfunction "1_1") (pintype "passive"))
    )
    (net (code "48") (name "Net-(OC5A-A)") (class "Default")
      (node (ref "OC5") (pin "1") (pinfunction "A_1") (pintype "passive"))
      (node (ref "RC45") (pin "1") (pinfunction "1_1") (pintype "passive"))
    )
    (net (code "49") (name "Net-(OC5B-A)") (class "Default")
      (node (ref "OC5") (pin "3") (pinfunction "A_3") (pintype "passive"))
      (node (ref "RC49") (pin "1") (pinfunction "1_1") (pintype "passive"))
    )
    (net (code "50") (name "Net-(OC5C-A)") (class "Default")
      (node (ref "OC5") (pin "5") (pinfunction "A_5") (pintype "passive"))
      (node (ref "RC46") (pin "1") (pinfunction "1_1") (pintype "passive"))
    )
    (net (code "51") (name "Net-(OC5D-A)") (class "Default")
      (node (ref "OC5") (pin "7") (pinfunction "A_7") (pintype "passive"))
      (node (ref "RC47") (pin "1") (pinfunction "1_1") (pintype "passive"))
    )
    (net (code "52") (name "Net-(OC6A-A)") (class "Default")
      (node (ref "OC6") (pin "1") (pinfunction "A_1") (pintype "passive"))
      (node (ref "RC41") (pin "1") (pinfunction "1_1") (pintype "passive"))
    )
    (net (code "53") (name "Net-(OC6B-A)") (class "Default")
      (node (ref "OC6") (pin "3") (pinfunction "A_3") (pintype "passive"))
      (node (ref "RC42") (pin "1") (pinfunction "1_1") (pintype "passive"))
    )
    (net (code "54") (name "Net-(OC6C-A)") (class "Default")
      (node (ref "OC6") (pin "5") (pinfunction "A_5") (pintype "passive"))
      (node (ref "RC43") (pin "1") (pinfunction "1_1") (pintype "passive"))
    )
    (net (code "55") (name "Net-(OC6D-A)") (class "Default")
      (node (ref "OC6") (pin "7") (pinfunction "A_7") (pintype "passive"))
      (node (ref "RC44") (pin "1") (pinfunction "1_1") (pintype "passive"))
    )
    (net (code "56") (name "Net-(PFET-1-G)") (class "Default")
      (node (ref "D2") (pin "A") (pinfunction "A_A") (pintype "passive"))
      (node (ref "PFET-1") (pin "1") (pinfunction "G_1") (pintype "passive"))
      (node (ref "R7") (pin "1") (pinfunction "1_1") (pintype "passive"))
    )
    (net (code "57") (name "Net-(PWR-LED-PadA)") (class "Default")
      (node (ref "PWR-LED") (pin "A") (pinfunction "A_A") (pintype "passive"))
      (node (ref "RPL") (pin "1") (pinfunction "1_1") (pintype "passive"))
    )
    (net (code "58") (name "Net-(PWR-LED1-PadA)") (class "Default")
      (node (ref "PWR-LED1") (pin "A") (pinfunction "A_A") (pintype "passive"))
      (node (ref "R15") (pin "1") (pinfunction "1_1") (pintype "passive"))
    )
    (net (code "59") (name "Net-(Q3-B)") (class "Default")
      (node (ref "Q3") (pin "1") (pinfunction "B_1") (pintype "passive"))
      (node (ref "R16") (pin "1") (pinfunction "1_1") (pintype "passive"))
    )
    (net (code "60") (name "Net-(Q3-E)") (class "Default")
      (node (ref "Q3") (pin "2") (pinfunction "E_2") (pintype "passive"))
      (node (ref "RC3") (pin "2") (pinfunction "2_2") (pintype "passive"))
    )
    (net (code "61") (name "Net-(U$40-A1)") (class "Default")
      (node (ref "R35") (pin "2") (pinfunction "2_2") (pintype "passive"))
      (node (ref "U$37") (pin "FLAG") (pinfunction "FLAG_FLAG") (pintype "bidirectional"))
      (node (ref "U$40") (pin "1") (pinfunction "A1_1") (pintype "bidirectional"))
    )
    (net (code "62") (name "Net-(U$40-A2)") (class "Default")
      (node (ref "R33") (pin "1") (pinfunction "1_1") (pintype "passive"))
      (node (ref "U$40") (pin "2") (pinfunction "A2_2") (pintype "bidirectional"))
    )
    (net (code "63") (name "Net-(U$40-Y1)") (class "Default")
      (node (ref "PWR-LED1") (pin "C") (pinfunction "C_C") (pintype "passive"))
      (node (ref "U$40") (pin "5") (pinfunction "Y1_5") (pintype "bidirectional"))
    )
    (net (code "64") (name "Net-(U$40-Y2)") (class "Default")
      (node (ref "R15_BYPASS8") (pin "2") (pinfunction "2_2") (pintype "passive"))
      (node (ref "U$40") (pin "6") (pinfunction "Y2_6") (pintype "bidirectional"))
    )
    (net (code "65") (name "Net-(Z1-B)") (class "Default")
      (node (ref "R4") (pin "1") (pinfunction "1_1") (pintype "passive"))
      (node (ref "Z1") (pin "1") (pinfunction "B_1") (pintype "passive"))
    )
    (net (code "66") (name "Net-(Z2-B)") (class "Default")
      (node (ref "R8") (pin "1") (pinfunction "1_1") (pintype "passive"))
      (node (ref "Z2") (pin "1") (pinfunction "B_1") (pintype "passive"))
    )
    (net (code "67") (name "Net-(Z3-B)") (class "Default")
      (node (ref "R3") (pin "1") (pinfunction "1_1") (pintype "passive"))
      (node (ref "Z3") (pin "1") (pinfunction "B_1") (pintype "passive"))
    )
    (net (code "68") (name "Net-(Z4-B)") (class "Default")
      (node (ref "R9") (pin "1") (pinfunction "1_1") (pintype "passive"))
      (node (ref "Z4") (pin "1") (pinfunction "B_1") (pintype "passive"))
    )
    (net (code "69") (name "Net-(Z5-B)") (class "Default")
      (node (ref "R10") (pin "1") (pinfunction "1_1") (pintype "passive"))
      (node (ref "Z5") (pin "1") (pinfunction "B_1") (pintype "passive"))
    )
    (net (code "70") (name "Net-(Z6-B)") (class "Default")
      (node (ref "R11") (pin "1") (pinfunction "1_1") (pintype "passive"))
      (node (ref "Z6") (pin "1") (pinfunction "B_1") (pintype "passive"))
    )
    (net (code "71") (name "Net-(Z7-B)") (class "Default")
      (node (ref "R12") (pin "1") (pinfunction "1_1") (pintype "passive"))
      (node (ref "Z7") (pin "1") (pinfunction "B_1") (pintype "passive"))
    )
    (net (code "72") (name "Net-(Z8-B)") (class "Default")
      (node (ref "R13") (pin "1") (pinfunction "1_1") (pintype "passive"))
      (node (ref "Z8") (pin "1") (pinfunction "B_1") (pintype "passive"))
    )
    (net (code "73") (name "Net-(Z9-B)") (class "Default")
      (node (ref "R14") (pin "1") (pinfunction "1_1") (pintype "passive"))
      (node (ref "Z9") (pin "1") (pinfunction "B_1") (pintype "passive"))
    )
    (net (code "74") (name "OVLO") (class "Default")
      (node (ref "ADJUST_OVLO") (pin "1") (pinfunction "1_1") (pintype "passive"))
      (node (ref "R31") (pin "2") (pinfunction "2_2") (pintype "passive"))
      (node (ref "U$37") (pin "OVLO") (pinfunction "OVLO_OVLO") (pintype "bidirectional"))
    )
    (net (code "75") (name "RESET") (class "Default")
      (node (ref "C15") (pin "1") (pinfunction "1_1") (pintype "passive"))
      (node (ref "D1") (pin "A") (pinfunction "A_A") (pintype "passive"))
      (node (ref "IC12") (pin "30") (pinfunction "RESET_30") (pintype "input"))
      (node (ref "R6") (pin "1") (pinfunction "1_1") (pintype "passive"))
      (node (ref "RESET") (pin "1") (pinfunction "1_1") (pintype "passive"))
      (node (ref "RRST") (pin "1") (pinfunction "1_1") (pintype "passive"))
      (node (ref "U$1") (pin "RESET") (pinfunction "RST_RESET") (pintype "bidirectional"))
      (node (ref "U$1") (pin "RST") (pinfunction "RST_RST") (pintype "bidirectional"))
    )
    (net (code "76") (name "RFID-EN1") (class "Default")
      (node (ref "IC12") (pin "58") (pinfunction "(A13)PC5_58") (pintype "bidirectional"))
      (node (ref "R69") (pin "1") (pinfunction "1_1") (pintype "passive"))
      (node (ref "U2") (pin "5") (pinfunction "1DE/~{RE}_5") (pintype "input"))
    )
    (net (code "77") (name "RFID-EN2") (class "Default")
      (node (ref "IC12") (pin "56") (pinfunction "(A11)PC3_56") (pintype "bidirectional"))
      (node (ref "R20") (pin "1") (pinfunction "1_1") (pintype "passive"))
      (node (ref "U2") (pin "7") (pinfunction "2DE/~{RE}_7") (pintype "input"))
    )
    (net (code "78") (name "RFID-EN3") (class "Default")
      (node (ref "IC12") (pin "54") (pinfunction "(A9)PC1_54") (pintype "bidirectional"))
      (node (ref "R21") (pin "1") (pinfunction "1_1") (pintype "passive"))
      (node (ref "U2") (pin "9") (pinfunction "3DE/~{RE}_9") (pintype "input"))
    )
    (net (code "79") (name "RFID-EN4") (class "Default")
      (node (ref "IC12") (pin "50") (pinfunction "(T0)PD7_50") (pintype "bidirectional"))
      (node (ref "R22") (pin "1") (pinfunction "1_1") (pintype "passive"))
      (node (ref "U2") (pin "11") (pinfunction "4DE/~{RE}_11") (pintype "input"))
    )
    (net (code "80") (name "RFID-EN5") (class "Default")
      (node (ref "IC12") (pin "52") (pinfunction "(RD)PG1_52") (pintype "bidirectional"))
      (node (ref "R23") (pin "1") (pinfunction "1_1") (pintype "passive"))
      (node (ref "U2") (pin "20") (pinfunction "5DE/~{RE}_20") (pintype "input"))
    )
    (net (code "81") (name "RFID-EN6") (class "Default")
      (node (ref "IC12") (pin "42") (pinfunction "PL7_42") (pintype "bidirectional"))
      (node (ref "R24") (pin "1") (pinfunction "1_1") (pintype "passive"))
      (node (ref "U2") (pin "22") (pinfunction "6DE/~{RE}_22") (pintype "input"))
    )
    (net (code "82") (name "RFID-EN7") (class "Default")
      (node (ref "IC12") (pin "40") (pinfunction "PL5(OC5C)_40") (pintype "bidirectional"))
      (node (ref "R25") (pin "1") (pinfunction "1_1") (pintype "passive"))
      (node (ref "U2") (pin "24") (pinfunction "7DE/~{RE}_24") (pintype "input"))
    )
    (net (code "83") (name "RFID-EN8") (class "Default")
      (node (ref "IC12") (pin "38") (pinfunction "PL3(OC5A)_38") (pintype "bidirectional"))
      (node (ref "R26") (pin "1") (pinfunction "1_1") (pintype "passive"))
      (node (ref "U2") (pin "26") (pinfunction "8DE/~{RE}_26") (pintype "input"))
    )
    (net (code "84") (name "RFID-EN9") (class "Default")
      (node (ref "IC12") (pin "36") (pinfunction "PL1(ICP5)_36") (pintype "bidirectional"))
      (node (ref "R27") (pin "1") (pinfunction "1_1") (pintype "passive"))
      (node (ref "U2") (pin "28") (pinfunction "9DE/~{RE}_28") (pintype "input"))
    )
    (net (code "85") (name "RFID-TX1") (class "Default")
      (node (ref "IC12") (pin "59") (pinfunction "(A14)PC6_59") (pintype "bidirectional"))
      (node (ref "U2") (pin "4") (pinfunction "1A_4") (pintype "bidirectional"))
    )
    (net (code "86") (name "RFID-TX2") (class "Default")
      (node (ref "IC12") (pin "57") (pinfunction "(A12)PC4_57") (pintype "bidirectional"))
      (node (ref "U2") (pin "6") (pinfunction "2A_6") (pintype "bidirectional"))
    )
    (net (code "87") (name "RFID-TX3") (class "Default")
      (node (ref "IC12") (pin "55") (pinfunction "(A10)PC2_55") (pintype "bidirectional"))
      (node (ref "U2") (pin "8") (pinfunction "3A_8") (pintype "bidirectional"))
    )
    (net (code "88") (name "RFID-TX4") (class "Default")
      (node (ref "IC12") (pin "53") (pinfunction "(A8)PC0_53") (pintype "bidirectional"))
      (node (ref "U2") (pin "10") (pinfunction "4A_10") (pintype "bidirectional"))
    )
    (net (code "89") (name "RFID-TX5") (class "Default")
      (node (ref "IC12") (pin "70") (pinfunction "(ALE)PG2_70") (pintype "bidirectional"))
      (node (ref "U2") (pin "19") (pinfunction "5A_19") (pintype "bidirectional"))
    )
    (net (code "90") (name "RFID-TX6") (class "Default")
      (node (ref "IC12") (pin "51") (pinfunction "(WR)PG0_51") (pintype "bidirectional"))
      (node (ref "U2") (pin "21") (pinfunction "6A_21") (pintype "bidirectional"))
    )
    (net (code "91") (name "RFID-TX7") (class "Default")
      (node (ref "IC12") (pin "41") (pinfunction "PL6_41") (pintype "bidirectional"))
      (node (ref "U2") (pin "23") (pinfunction "7A_23") (pintype "bidirectional"))
    )
    (net (code "92") (name "RFID-TX8") (class "Default")
      (node (ref "IC12") (pin "39") (pinfunction "PL4(OC5B)_39") (pintype "bidirectional"))
      (node (ref "U2") (pin "25") (pinfunction "8A_25") (pintype "bidirectional"))
    )
    (net (code "93") (name "RFID-TX9") (class "Default")
      (node (ref "IC12") (pin "37") (pinfunction "PL2(T5)_37") (pintype "bidirectional"))
      (node (ref "U2") (pin "27") (pinfunction "9A_27") (pintype "bidirectional"))
    )
    (net (code "94") (name "RFID1+") (class "Default")
      (node (ref "R83") (pin "1") (pinfunction "1_1") (pintype "passive"))
      (node (ref "R86") (pin "2") (pinfunction "2_2") (pintype "passive"))
      (node (ref "U2") (pin "30") (pinfunction "1B+_30") (pintype "bidirectional"))
    )
    (net (code "95") (name "RFID1++") (class "Default")
      (node (ref "R85") (pin "2") (pinfunction "2_2") (pintype "passive"))
      (node (ref "R86") (pin "1") (pinfunction "1_1") (pintype "passive"))
      (node (ref "RFID-1") (pin "P$4") (pinfunction "P$4_P$4") (pintype "bidirectional"))
      (node (ref "U$14") (pin "C") (pinfunction "2_C") (pintype "bidirectional"))
    )
    (net (code "96") (name "RFID1-") (class "Default")
      (node (ref "R84") (pin "2") (pinfunction "2_2") (pintype "passive"))
      (node (ref "R87") (pin "2") (pinfunction "2_2") (pintype "passive"))
      (node (ref "U2") (pin "29") (pinfunction "1B-_29") (pintype "bidirectional"))
    )
    (net (code "97") (name "RFID1--") (class "Default")
      (node (ref "R85") (pin "1") (pinfunction "1_1") (pintype "passive"))
      (node (ref "R87") (pin "1") (pinfunction "1_1") (pintype "passive"))
      (node (ref "RFID-1") (pin "P$1") (pinfunction "P$1_P$1") (pintype "bidirectional"))
      (node (ref "U$4") (pin "C") (pinfunction "2_C") (pintype "bidirectional"))
    )
    (net (code "98") (name "RFID2+") (class "Default")
      (node (ref "R88") (pin "1") (pinfunction "1_1") (pintype "passive"))
      (node (ref "R91") (pin "2") (pinfunction "2_2") (pintype "passive"))
      (node (ref "U2") (pin "32") (pinfunction "2B+_32") (pintype "bidirectional"))
    )
    (net (code "99") (name "RFID2++") (class "Default")
      (node (ref "R90") (pin "2") (pinfunction "2_2") (pintype "passive"))
      (node (ref "R91") (pin "1") (pinfunction "1_1") (pintype "passive"))
      (node (ref "RFID-2") (pin "P$4") (pinfunction "P$4_P$4") (pintype "bidirectional"))
      (node (ref "U$16") (pin "C") (pinfunction "2_C") (pintype "bidirectional"))
    )
    (net (code "100") (name "RFID2-") (class "Default")
      (node (ref "R89") (pin "2") (pinfunction "2_2") (pintype "passive"))
      (node (ref "R92") (pin "2") (pinfunction "2_2") (pintype "passive"))
      (node (ref "U2") (pin "31") (pinfunction "2B-_31") (pintype "bidirectional"))
    )
    (net (code "101") (name "RFID2--") (class "Default")
      (node (ref "R90") (pin "1") (pinfunction "1_1") (pintype "passive"))
      (node (ref "R92") (pin "1") (pinfunction "1_1") (pintype "passive"))
      (node (ref "RFID-2") (pin "P$1") (pinfunction "P$1_P$1") (pintype "bidirectional"))
      (node (ref "U$15") (pin "C") (pinfunction "2_C") (pintype "bidirectional"))
    )
    (net (code "102") (name "RFID3+") (class "Default")
      (node (ref "R93") (pin "1") (pinfunction "1_1") (pintype "passive"))
      (node (ref "R96") (pin "2") (pinfunction "2_2") (pintype "passive"))
      (node (ref "U2") (pin "34") (pinfunction "3B+_34") (pintype "bidirectional"))
    )
    (net (code "103") (name "RFID3++") (class "Default")
      (node (ref "R95") (pin "2") (pinfunction "2_2") (pintype "passive"))
      (node (ref "R96") (pin "1") (pinfunction "1_1") (pintype "passive"))
      (node (ref "RFID-3") (pin "P$4") (pinfunction "P$4_P$4") (pintype "bidirectional"))
      (node (ref "U$18") (pin "C") (pinfunction "2_C") (pintype "bidirectional"))
    )
    (net (code "104") (name "RFID3-") (class "Default")
      (node (ref "R94") (pin "2") (pinfunction "2_2") (pintype "passive"))
      (node (ref "R97") (pin "2") (pinfunction "2_2") (pintype "passive"))
      (node (ref "U2") (pin "33") (pinfunction "3B-_33") (pintype "bidirectional"))
    )
    (net (code "105") (name "RFID3--") (class "Default")
      (node (ref "R95") (pin "1") (pinfunction "1_1") (pintype "passive"))
      (node (ref "R97") (pin "1") (pinfunction "1_1") (pintype "passive"))
      (node (ref "RFID-3") (pin "P$1") (pinfunction "P$1_P$1") (pintype "bidirectional"))
      (node (ref "U$17") (pin "C") (pinfunction "2_C") (pintype "bidirectional"))
    )
    (net (code "106") (name "RFID4+") (class "Default")
      (node (ref "R101") (pin "2") (pinfunction "2_2") (pintype "passive"))
      (node (ref "R98") (pin "1") (pinfunction "1_1") (pintype "passive"))
      (node (ref "U2") (pin "35") (pinfunction "4B-_35") (pintype "bidirectional"))
    )
    (net (code "107") (name "RFID4++") (class "Default")
      (node (ref "R100") (pin "2") (pinfunction "2_2") (pintype "passive"))
      (node (ref "R101") (pin "1") (pinfunction "1_1") (pintype "passive"))
      (node (ref "RFID-4") (pin "P$4") (pinfunction "P$4_P$4") (pintype "bidirectional"))
      (node (ref "U$20") (pin "C") (pinfunction "2_C") (pintype "bidirectional"))
    )
    (net (code "108") (name "RFID4-") (class "Default")
      (node (ref "R102") (pin "2") (pinfunction "2_2") (pintype "passive"))
      (node (ref "R99") (pin "2") (pinfunction "2_2") (pintype "passive"))
      (node (ref "U2") (pin "36") (pinfunction "4B+_36") (pintype "bidirectional"))
    )
    (net (code "109") (name "RFID4--") (class "Default")
      (node (ref "R100") (pin "1") (pinfunction "1_1") (pintype "passive"))
      (node (ref "R102") (pin "1") (pinfunction "1_1") (pintype "passive"))
      (node (ref "RFID-4") (pin "P$1") (pinfunction "P$1_P$1") (pintype "bidirectional"))
      (node (ref "U$19") (pin "C") (pinfunction "2_C") (pintype "bidirectional"))
    )
    (net (code "110") (name "RFID5+") (class "Default")
      (node (ref "R28") (pin "1") (pinfunction "1_1") (pintype "passive"))
      (node (ref "R34") (pin "2") (pinfunction "2_2") (pintype "passive"))
      (node (ref "U2") (pin "38") (pinfunction "5B+_38") (pintype "bidirectional"))
    )
    (net (code "111") (name "RFID5++") (class "Default")
      (node (ref "R30") (pin "2") (pinfunction "2_2") (pintype "passive"))
      (node (ref "R34") (pin "1") (pinfunction "1_1") (pintype "passive"))
      (node (ref "RFID-5") (pin "P$4") (pinfunction "P$4_P$4") (pintype "bidirectional"))
      (node (ref "U$22") (pin "C") (pinfunction "2_C") (pintype "bidirectional"))
    )
    (net (code "112") (name "RFID5-") (class "Default")
      (node (ref "R29") (pin "2") (pinfunction "2_2") (pintype "passive"))
      (node (ref "R36") (pin "2") (pinfunction "2_2") (pintype "passive"))
      (node (ref "U2") (pin "37") (pinfunction "5B-_37") (pintype "bidirectional"))
    )
    (net (code "113") (name "RFID5--") (class "Default")
      (node (ref "R30") (pin "1") (pinfunction "1_1") (pintype "passive"))
      (node (ref "R36") (pin "1") (pinfunction "1_1") (pintype "passive"))
      (node (ref "RFID-5") (pin "P$1") (pinfunction "P$1_P$1") (pintype "bidirectional"))
      (node (ref "U$21") (pin "C") (pinfunction "2_C") (pintype "bidirectional"))
    )
    (net (code "114") (name "RFID6+") (class "Default")
      (node (ref "R108") (pin "1") (pinfunction "1_1") (pintype "passive"))
      (node (ref "R111") (pin "2") (pinfunction "2_2") (pintype "passive"))
      (node (ref "U2") (pin "47") (pinfunction "6B+_47") (pintype "bidirectional"))
    )
    (net (code "115") (name "RFID6++") (class "Default")
      (node (ref "R110") (pin "2") (pinfunction "2_2") (pintype "passive"))
      (node (ref "R111") (pin "1") (pinfunction "1_1") (pintype "passive"))
      (node (ref "RFID-6") (pin "P$4") (pinfunction "P$4_P$4") (pintype "bidirectional"))
      (node (ref "U$24") (pin "C") (pinfunction "2_C") (pintype "bidirectional"))
    )
    (net (code "116") (name "RFID6-") (class "Default")
      (node (ref "R109") (pin "2") (pinfunction "2_2") (pintype "passive"))
      (node (ref "R112") (pin "2") (pinfunction "2_2") (pintype "passive"))
      (node (ref "U2") (pin "46") (pinfunction "6B-_46") (pintype "bidirectional"))
    )
    (net (code "117") (name "RFID6--") (class "Default")
      (node (ref "R110") (pin "1") (pinfunction "1_1") (pintype "passive"))
      (node (ref "R112") (pin "1") (pinfunction "1_1") (pintype "passive"))
      (node (ref "RFID-6") (pin "P$1") (pinfunction "P$1_P$1") (pintype "bidirectional"))
      (node (ref "U$23") (pin "C") (pinfunction "2_C") (pintype "bidirectional"))
    )
    (net (code "118") (name "RFID7+") (class "Default")
      (node (ref "R113") (pin "1") (pinfunction "1_1") (pintype "passive"))
      (node (ref "R116") (pin "2") (pinfunction "2_2") (pintype "passive"))
      (node (ref "U2") (pin "49") (pinfunction "7B+_49") (pintype "bidirectional"))
    )
    (net (code "119") (name "RFID7++") (class "Default")
      (node (ref "R115") (pin "2") (pinfunction "2_2") (pintype "passive"))
      (node (ref "R116") (pin "1") (pinfunction "1_1") (pintype "passive"))
      (node (ref "U$26") (pin "C") (pinfunction "2_C") (pintype "bidirectional"))
      (node (ref "U$53") (pin "P$4") (pinfunction "P$4_P$4") (pintype "bidirectional"))
    )
    (net (code "120") (name "RFID7-") (class "Default")
      (node (ref "R114") (pin "2") (pinfunction "2_2") (pintype "passive"))
      (node (ref "R117") (pin "2") (pinfunction "2_2") (pintype "passive"))
      (node (ref "U2") (pin "48") (pinfunction "7B-_48") (pintype "bidirectional"))
    )
    (net (code "121") (name "RFID7--") (class "Default")
      (node (ref "R115") (pin "1") (pinfunction "1_1") (pintype "passive"))
      (node (ref "R117") (pin "1") (pinfunction "1_1") (pintype "passive"))
      (node (ref "U$25") (pin "C") (pinfunction "2_C") (pintype "bidirectional"))
      (node (ref "U$53") (pin "P$1") (pinfunction "P$1_P$1") (pintype "bidirectional"))
    )
    (net (code "122") (name "RFID8+") (class "Default")
      (node (ref "R118") (pin "1") (pinfunction "1_1") (pintype "passive"))
      (node (ref "R121") (pin "2") (pinfunction "2_2") (pintype "passive"))
      (node (ref "U2") (pin "51") (pinfunction "8B+_51") (pintype "bidirectional"))
    )
    (net (code "123") (name "RFID8++") (class "Default")
      (node (ref "R120") (pin "2") (pinfunction "2_2") (pintype "passive"))
      (node (ref "R121") (pin "1") (pinfunction "1_1") (pintype "passive"))
      (node (ref "RFID-8") (pin "P$4") (pinfunction "P$4_P$4") (pintype "bidirectional"))
      (node (ref "U$28") (pin "C") (pinfunction "2_C") (pintype "bidirectional"))
    )
    (net (code "124") (name "RFID8-") (class "Default")
      (node (ref "R119") (pin "2") (pinfunction "2_2") (pintype "passive"))
      (node (ref "R122") (pin "2") (pinfunction "2_2") (pintype "passive"))
      (node (ref "U2") (pin "50") (pinfunction "8B-_50") (pintype "bidirectional"))
    )
    (net (code "125") (name "RFID8--") (class "Default")
      (node (ref "R120") (pin "1") (pinfunction "1_1") (pintype "passive"))
      (node (ref "R122") (pin "1") (pinfunction "1_1") (pintype "passive"))
      (node (ref "RFID-8") (pin "P$1") (pinfunction "P$1_P$1") (pintype "bidirectional"))
      (node (ref "U$27") (pin "C") (pinfunction "2_C") (pintype "bidirectional"))
    )
    (net (code "126") (name "RFID9+") (class "Default")
      (node (ref "R103") (pin "1") (pinfunction "1_1") (pintype "passive"))
      (node (ref "R106") (pin "2") (pinfunction "2_2") (pintype "passive"))
      (node (ref "U2") (pin "53") (pinfunction "9B+_53") (pintype "bidirectional"))
    )
    (net (code "127") (name "RFID9++") (class "Default")
      (node (ref "R105") (pin "2") (pinfunction "2_2") (pintype "passive"))
      (node (ref "R106") (pin "1") (pinfunction "1_1") (pintype "passive"))
      (node (ref "RFID-7") (pin "P$4") (pinfunction "P$4_P$4") (pintype "bidirectional"))
      (node (ref "U$30") (pin "C") (pinfunction "2_C") (pintype "bidirectional"))
    )
    (net (code "128") (name "RFID9-") (class "Default")
      (node (ref "R104") (pin "2") (pinfunction "2_2") (pintype "passive"))
      (node (ref "R107") (pin "2") (pinfunction "2_2") (pintype "passive"))
      (node (ref "U2") (pin "52") (pinfunction "9B-_52") (pintype "bidirectional"))
    )
    (net (code "129") (name "RFID9--") (class "Default")
      (node (ref "R105") (pin "1") (pinfunction "1_1") (pintype "passive"))
      (node (ref "R107") (pin "1") (pinfunction "1_1") (pintype "passive"))
      (node (ref "RFID-7") (pin "P$1") (pinfunction "P$1_P$1") (pintype "bidirectional"))
      (node (ref "U$29") (pin "C") (pinfunction "2_C") (pintype "bidirectional"))
    )
    (net (code "130") (name "RGB-CH1") (class "Default")
      (node (ref "C2") (pin "1") (pinfunction "1_1") (pintype "passive"))
      (node (ref "IC12") (pin "6") (pinfunction "(OC3B/INT4)PE4_6") (pintype "bidirectional"))
      (node (ref "RGB") (pin "2") (pinfunction "S_2") (pintype "passive"))
    )
    (net (code "131") (name "RX_1") (class "Default")
      (node (ref "IC12") (pin "3") (pinfunction "(TXD0)PE1_3") (pintype "bidirectional"))
      (node (ref "U$1") (pin "RX_1") (pinfunction "RX_1_RX_1") (pintype "bidirectional"))
    )
    (net (code "132") (name "SCK") (class "Default")
      (node (ref "IC12") (pin "20") (pinfunction "(SCK/PCINT1)PB1_20") (pintype "bidirectional"))
      (node (ref "SPI") (pin "3") (pinfunction "S_3") (pintype "passive"))
      (node (ref "SPI-1") (pin "3") (pinfunction "S_3") (pintype "passive"))
      (node (ref "SPI-2") (pin "3") (pinfunction "S_3") (pintype "passive"))
      (node (ref "U$1") (pin "SCK") (pinfunction "SCK_SCK") (pintype "bidirectional"))
      (node (ref "U$33") (pin "3") (pinfunction "K1K2_3") (pintype "passive"))
    )
    (net (code "133") (name "SCL") (class "Default")
      (node (ref "I2C-1") (pin "3") (pinfunction "S_3") (pintype "passive"))
      (node (ref "I2C-2") (pin "3") (pinfunction "S_3") (pintype "passive"))
      (node (ref "IC12") (pin "43") (pinfunction "(SCL/INT0)PD0_43") (pintype "bidirectional"))
      (node (ref "R2") (pin "2") (pinfunction "2_2") (pintype "passive"))
      (node (ref "U$36") (pin "3") (pinfunction "K1K2_3") (pintype "passive"))
    )
    (net (code "134") (name "SDA") (class "Default")
      (node (ref "I2C-1") (pin "2") (pinfunction "S_2") (pintype "passive"))
      (node (ref "I2C-2") (pin "2") (pinfunction "S_2") (pintype "passive"))
      (node (ref "IC12") (pin "44") (pinfunction "(SDA/INT1)PD1_44") (pintype "bidirectional"))
      (node (ref "R1") (pin "2") (pinfunction "2_2") (pintype "passive"))
      (node (ref "U$35") (pin "3") (pinfunction "K1K2_3") (pintype "passive"))
    )
    (net (code "135") (name "SETI") (class "Default")
      (node (ref "R17") (pin "1") (pinfunction "1_1") (pintype "passive"))
      (node (ref "U$37") (pin "SETI") (pinfunction "SETI_SETI") (pintype "bidirectional"))
    )
    (net (code "136") (name "TRAY_LOCK_CONTROL_EM_1") (class "Default")
      (node (ref "RC6") (pin "2") (pinfunction "2_2") (pintype "passive"))
      (node (ref "U$13") (pin "3") (pinfunction "3_3") (pintype "bidirectional"))
      (node (ref "Z3") (pin "3") (pinfunction "E_3") (pintype "passive"))
    )
    (net (code "137") (name "TRAY_LOCK_CONTROL_EM_2") (class "Default")
      (node (ref "RC9") (pin "2") (pinfunction "2_2") (pintype "passive"))
      (node (ref "U$12") (pin "3") (pinfunction "3_3") (pintype "bidirectional"))
      (node (ref "Z1") (pin "3") (pinfunction "E_3") (pintype "passive"))
    )
    (net (code "138") (name "TRAY_LOCK_CONTROL_EM_3") (class "Default")
      (node (ref "RC11") (pin "2") (pinfunction "2_2") (pintype "passive"))
      (node (ref "U$5") (pin "3") (pinfunction "3_3") (pintype "bidirectional"))
      (node (ref "Z2") (pin "3") (pinfunction "E_3") (pintype "passive"))
    )
    (net (code "139") (name "TRAY_LOCK_CONTROL_EM_4") (class "Default")
      (node (ref "RC13") (pin "2") (pinfunction "2_2") (pintype "passive"))
      (node (ref "U$6") (pin "3") (pinfunction "3_3") (pintype "bidirectional"))
      (node (ref "Z4") (pin "3") (pinfunction "E_3") (pintype "passive"))
    )
    (net (code "140") (name "TRAY_LOCK_CONTROL_EM_5") (class "Default")
      (node (ref "RC15") (pin "2") (pinfunction "2_2") (pintype "passive"))
      (node (ref "U$7") (pin "3") (pinfunction "3_3") (pintype "bidirectional"))
      (node (ref "Z5") (pin "3") (pinfunction "E_3") (pintype "passive"))
    )
    (net (code "141") (name "TRAY_LOCK_CONTROL_EM_6") (class "Default")
      (node (ref "RC17") (pin "2") (pinfunction "2_2") (pintype "passive"))
      (node (ref "U$8") (pin "3") (pinfunction "3_3") (pintype "bidirectional"))
      (node (ref "Z6") (pin "3") (pinfunction "E_3") (pintype "passive"))
    )
    (net (code "142") (name "TRAY_LOCK_CONTROL_EM_7") (class "Default")
      (node (ref "RC19") (pin "2") (pinfunction "2_2") (pintype "passive"))
      (node (ref "U$9") (pin "3") (pinfunction "3_3") (pintype "bidirectional"))
      (node (ref "Z7") (pin "3") (pinfunction "E_3") (pintype "passive"))
    )
    (net (code "143") (name "TRAY_LOCK_CONTROL_EM_8") (class "Default")
      (node (ref "RC21") (pin "2") (pinfunction "2_2") (pintype "passive"))
      (node (ref "U$10") (pin "3") (pinfunction "3_3") (pintype "bidirectional"))
      (node (ref "Z8") (pin "3") (pinfunction "E_3") (pintype "passive"))
    )
    (net (code "144") (name "TRAY_LOCK_CONTROL_EM_9") (class "Default")
      (node (ref "RC23") (pin "2") (pinfunction "2_2") (pintype "passive"))
      (node (ref "U$11") (pin "3") (pinfunction "3_3") (pintype "bidirectional"))
      (node (ref "Z9") (pin "3") (pinfunction "E_3") (pintype "passive"))
    )
    (net (code "145") (name "TRAY_LOCK_CONTROL_UC_1") (class "Default")
      (node (ref "IC12") (pin "5") (pinfunction "(OC3A/AIN1)PE3_5") (pintype "bidirectional"))
      (node (ref "OC1") (pin "2") (pinfunction "C_2") (pintype "passive"))
    )
    (net (code "146") (name "TRAY_LOCK_CONTROL_UC_2") (class "Default")
      (node (ref "IC12") (pin "15") (pinfunction "PH3(OC4A)_15") (pintype "bidirectional"))
      (node (ref "OC1") (pin "4") (pinfunction "C_4") (pintype "passive"))
    )
    (net (code "147") (name "TRAY_LOCK_CONTROL_UC_3") (class "Default")
      (node (ref "IC12") (pin "16") (pinfunction "PH4(OC4B)_16") (pintype "bidirectional"))
      (node (ref "OC1") (pin "6") (pinfunction "C_6") (pintype "passive"))
    )
    (net (code "148") (name "TRAY_LOCK_CONTROL_UC_4") (class "Default")
      (node (ref "IC12") (pin "17") (pinfunction "PH5(OC4C)_17") (pintype "bidirectional"))
      (node (ref "OC1") (pin "8") (pinfunction "C_8") (pintype "passive"))
    )
    (net (code "149") (name "TRAY_LOCK_CONTROL_UC_5") (class "Default")
      (node (ref "IC12") (pin "18") (pinfunction "PH6(OC2B)_18") (pintype "bidirectional"))
      (node (ref "OC2") (pin "2") (pinfunction "C_2") (pintype "passive"))
    )
    (net (code "150") (name "TRAY_LOCK_CONTROL_UC_6") (class "Default")
      (node (ref "IC12") (pin "23") (pinfunction "(OC2A/PCINT4)PB4_23") (pintype "bidirectional"))
      (node (ref "OC2") (pin "4") (pinfunction "C_4") (pintype "passive"))
    )
    (net (code "151") (name "TRAY_LOCK_CONTROL_UC_7") (class "Default")
      (node (ref "IC12") (pin "24") (pinfunction "(OC1A/PCINT5)PB5_24") (pintype "bidirectional"))
      (node (ref "OC2") (pin "6") (pinfunction "C_6") (pintype "passive"))
    )
    (net (code "152") (name "TRAY_LOCK_CONTROL_UC_8") (class "Default")
      (node (ref "IC12") (pin "25") (pinfunction "(OC1B/PCINT6)PB6_25") (pintype "bidirectional"))
      (node (ref "OC2") (pin "8") (pinfunction "C_8") (pintype "passive"))
    )
    (net (code "153") (name "TRAY_LOCK_CONTROL_UC_9") (class "Default")
      (node (ref "IC12") (pin "26") (pinfunction "(OC0A/OC1C/PCINT7)PB7_26") (pintype "bidirectional"))
      (node (ref "OC4") (pin "2") (pinfunction "C_2") (pintype "passive"))
    )
    (net (code "154") (name "TRAY_LOCK_STATUS_1") (class "Default")
      (node (ref "IC12") (pin "78") (pinfunction "(AD0)PA0_78") (pintype "bidirectional"))
      (node (ref "OC6") (pin "16") (pinfunction "COL_16") (pintype "passive"))
      (node (ref "RC30") (pin "1") (pinfunction "1_1") (pintype "passive"))
    )
    (net (code "155") (name "TRAY_LOCK_STATUS_1#") (class "Default")
      (node (ref "OC6") (pin "2") (pinfunction "C_2") (pintype "passive"))
      (node (ref "U$13") (pin "5") (pinfunction "5_5") (pintype "bidirectional"))
    )
    (net (code "156") (name "TRAY_LOCK_STATUS_2") (class "Default")
      (node (ref "IC12") (pin "77") (pinfunction "(AD1)PA1_77") (pintype "bidirectional"))
      (node (ref "OC6") (pin "14") (pinfunction "COL_14") (pintype "passive"))
      (node (ref "RC31") (pin "1") (pinfunction "1_1") (pintype "passive"))
    )
    (net (code "157") (name "TRAY_LOCK_STATUS_2#") (class "Default")
      (node (ref "OC6") (pin "4") (pinfunction "C_4") (pintype "passive"))
      (node (ref "U$12") (pin "5") (pinfunction "5_5") (pintype "bidirectional"))
    )
    (net (code "158") (name "TRAY_LOCK_STATUS_3") (class "Default")
      (node (ref "IC12") (pin "76") (pinfunction "(AD2)PA2_76") (pintype "bidirectional"))
      (node (ref "OC6") (pin "12") (pinfunction "COL_12") (pintype "passive"))
      (node (ref "RC34") (pin "1") (pinfunction "1_1") (pintype "passive"))
    )
    (net (code "159") (name "TRAY_LOCK_STATUS_3#") (class "Default")
      (node (ref "OC6") (pin "6") (pinfunction "C_6") (pintype "passive"))
      (node (ref "U$5") (pin "5") (pinfunction "5_5") (pintype "bidirectional"))
    )
    (net (code "160") (name "TRAY_LOCK_STATUS_4") (class "Default")
      (node (ref "IC12") (pin "75") (pinfunction "(AD3)PA3_75") (pintype "bidirectional"))
      (node (ref "OC6") (pin "10") (pinfunction "COL_10") (pintype "passive"))
      (node (ref "RC35") (pin "1") (pinfunction "1_1") (pintype "passive"))
    )
    (net (code "161") (name "TRAY_LOCK_STATUS_4#") (class "Default")
      (node (ref "OC6") (pin "8") (pinfunction "C_8") (pintype "passive"))
      (node (ref "U$6") (pin "5") (pinfunction "5_5") (pintype "bidirectional"))
    )
    (net (code "162") (name "TRAY_LOCK_STATUS_5") (class "Default")
      (node (ref "IC12") (pin "74") (pinfunction "(AD4)PA4_74") (pintype "bidirectional"))
      (node (ref "OC5") (pin "16") (pinfunction "COL_16") (pintype "passive"))
      (node (ref "RC36") (pin "1") (pinfunction "1_1") (pintype "passive"))
    )
    (net (code "163") (name "TRAY_LOCK_STATUS_5#") (class "Default")
      (node (ref "OC5") (pin "2") (pinfunction "C_2") (pintype "passive"))
      (node (ref "U$7") (pin "5") (pinfunction "5_5") (pintype "bidirectional"))
    )
    (net (code "164") (name "TRAY_LOCK_STATUS_6") (class "Default")
      (node (ref "IC12") (pin "73") (pinfunction "(AD5)PA5_73") (pintype "bidirectional"))
      (node (ref "OC5") (pin "14") (pinfunction "COL_14") (pintype "passive"))
      (node (ref "RC37") (pin "1") (pinfunction "1_1") (pintype "passive"))
    )
    (net (code "165") (name "TRAY_LOCK_STATUS_6#") (class "Default")
      (node (ref "OC5") (pin "4") (pinfunction "C_4") (pintype "passive"))
      (node (ref "U$8") (pin "5") (pinfunction "5_5") (pintype "bidirectional"))
    )
    (net (code "166") (name "TRAY_LOCK_STATUS_7") (class "Default")
      (node (ref "IC12") (pin "72") (pinfunction "(AD6)PA6_72") (pintype "bidirectional"))
      (node (ref "OC5") (pin "12") (pinfunction "COL_12") (pintype "passive"))
      (node (ref "RC38") (pin "1") (pinfunction "1_1") (pintype "passive"))
    )
    (net (code "167") (name "TRAY_LOCK_STATUS_7#") (class "Default")
      (node (ref "OC5") (pin "6") (pinfunction "C_6") (pintype "passive"))
      (node (ref "U$9") (pin "5") (pinfunction "5_5") (pintype "bidirectional"))
    )
    (net (code "168") (name "TRAY_LOCK_STATUS_8") (class "Default")
      (node (ref "IC12") (pin "71") (pinfunction "(AD7)PA7_71") (pintype "bidirectional"))
      (node (ref "OC5") (pin "10") (pinfunction "COL_10") (pintype "passive"))
      (node (ref "RC39") (pin "1") (pinfunction "1_1") (pintype "passive"))
    )
    (net (code "169") (name "TRAY_LOCK_STATUS_8#") (class "Default")
      (node (ref "OC5") (pin "8") (pinfunction "C_8") (pintype "passive"))
      (node (ref "U$10") (pin "5") (pinfunction "5_5") (pintype "bidirectional"))
    )
    (net (code "170") (name "TRAY_LOCK_STATUS_9") (class "Default")
      (node (ref "IC12") (pin "60") (pinfunction "(A15)PC7_60") (pintype "bidirectional"))
      (node (ref "OC4") (pin "10") (pinfunction "COL_10") (pintype "passive"))
      (node (ref "RC40") (pin "1") (pinfunction "1_1") (pintype "passive"))
    )
    (net (code "171") (name "TRAY_LOCK_STATUS_9#") (class "Default")
      (node (ref "OC4") (pin "8") (pinfunction "C_8") (pintype "passive"))
      (node (ref "U$11") (pin "5") (pinfunction "5_5") (pintype "bidirectional"))
    )
    (net (code "172") (name "TX_0") (class "Default")
      (node (ref "IC12") (pin "2") (pinfunction "(RXD0/PCIN8)PE0_2") (pintype "bidirectional"))
      (node (ref "U$1") (pin "TX_0") (pinfunction "TX_0_TX_0") (pintype "bidirectional"))
    )
    (net (code "173") (name "UVLO") (class "Default")
      (node (ref "ADJUST_UVLO") (pin "1") (pinfunction "1_1") (pintype "passive"))
      (node (ref "R32") (pin "2") (pinfunction "2_2") (pintype "passive"))
      (node (ref "U$37") (pin "UVLO") (pinfunction "UVLO_UVLO") (pintype "bidirectional"))
    )
    (net (code "174") (name "XTAL1") (class "Default")
      (node (ref "IC12") (pin "34") (pinfunction "XTAL1_34") (pintype "input"))
      (node (ref "R5") (pin "1") (pinfunction "1_1") (pintype "passive"))
      (node (ref "Y1") (pin "3") (pinfunction "3_3") (pintype "passive"))
    )
    (net (code "175") (name "XTAL2") (class "Default")
      (node (ref "IC12") (pin "33") (pinfunction "XTAL2_33") (pintype "output"))
      (node (ref "R5") (pin "2") (pinfunction "2_2") (pintype "passive"))
      (node (ref "Y1") (pin "1") (pinfunction "1_1") (pintype "passive"))
    )
    (net (code "176") (name "unconnected-(12V_POWER_JACK-Pad2)") (class "Default")
      (node (ref "12V_POWER_JACK") (pin "2") (pinfunction "2_2") (pintype "passive"))
    )
    (net (code "177") (name "unconnected-(IC12-(CLKO{slash}ICP3{slash}INT7)PE7-Pad9)") (class "Default")
      (node (ref "IC12") (pin "9") (pinfunction "(CLKO/ICP3/INT7)PE7_9") (pintype "bidirectional"))
    )
    (net (code "178") (name "unconnected-(IC12-(ICP1)PD4-Pad47)") (class "Default")
      (node (ref "IC12") (pin "47") (pinfunction "(ICP1)PD4_47") (pintype "bidirectional"))
    )
    (net (code "179") (name "unconnected-(IC12-(RXD1{slash}INT2)PD2-Pad45)") (class "Default")
      (node (ref "IC12") (pin "45") (pinfunction "(RXD1/INT2)PD2_45") (pintype "bidirectional"))
    )
    (net (code "180") (name "unconnected-(IC12-(T1)PD6-Pad49)") (class "Default")
      (node (ref "IC12") (pin "49") (pinfunction "(T1)PD6_49") (pintype "bidirectional"))
    )
    (net (code "181") (name "unconnected-(IC12-(T3{slash}INT6)PE6-Pad8)") (class "Default")
      (node (ref "IC12") (pin "8") (pinfunction "(T3/INT6)PE6_8") (pintype "bidirectional"))
    )
    (net (code "182") (name "unconnected-(IC12-(TOSC1)PG4-Pad29)") (class "Default")
      (node (ref "IC12") (pin "29") (pinfunction "(TOSC1)PG4_29") (pintype "bidirectional"))
    )
    (net (code "183") (name "unconnected-(IC12-(TOSC2)PG3-Pad28)") (class "Default")
      (node (ref "IC12") (pin "28") (pinfunction "(TOSC2)PG3_28") (pintype "bidirectional"))
    )
    (net (code "184") (name "unconnected-(IC12-(TXD1{slash}INT3)PD3-Pad46)") (class "Default")
      (node (ref "IC12") (pin "46") (pinfunction "(TXD1/INT3)PD3_46") (pintype "bidirectional"))
    )
    (net (code "185") (name "unconnected-(IC12-(XCK0{slash}AIN0)PE2-Pad4)") (class "Default")
      (node (ref "IC12") (pin "4") (pinfunction "(XCK0/AIN0)PE2_4") (pintype "bidirectional"))
    )
    (net (code "186") (name "unconnected-(IC12-(XCK1)PD5-Pad48)") (class "Default")
      (node (ref "IC12") (pin "48") (pinfunction "(XCK1)PD5_48") (pintype "bidirectional"))
    )
    (net (code "187") (name "unconnected-(IC12-PH0(RXD2)-Pad12)") (class "Default")
      (node (ref "IC12") (pin "12") (pinfunction "PH0(RXD2)_12") (pintype "bidirectional"))
    )
    (net (code "188") (name "unconnected-(IC12-PH1(TXD2)-Pad13)") (class "Default")
      (node (ref "IC12") (pin "13") (pinfunction "PH1(TXD2)_13") (pintype "bidirectional"))
    )
    (net (code "189") (name "unconnected-(IC12-PH2(XCK2)-Pad14)") (class "Default")
      (node (ref "IC12") (pin "14") (pinfunction "PH2(XCK2)_14") (pintype "bidirectional"))
    )
    (net (code "190") (name "unconnected-(IC12-PH7(T4)-Pad27)") (class "Default")
      (node (ref "IC12") (pin "27") (pinfunction "PH7(T4)_27") (pintype "bidirectional"))
    )
    (net (code "191") (name "unconnected-(IC12-PJ0(RXD3{slash}PCINT9)-Pad63)") (class "Default")
      (node (ref "IC12") (pin "63") (pinfunction "PJ0(RXD3/PCINT9)_63") (pintype "bidirectional"))
    )
    (net (code "192") (name "unconnected-(IC12-PJ1(TXD3{slash}PCINT10)-Pad64)") (class "Default")
      (node (ref "IC12") (pin "64") (pinfunction "PJ1(TXD3/PCINT10)_64") (pintype "bidirectional"))
    )
    (net (code "193") (name "unconnected-(IC12-PJ2(XCK3{slash}PCINT11)-Pad65)") (class "Default")
      (node (ref "IC12") (pin "65") (pinfunction "PJ2(XCK3/PCINT11)_65") (pintype "bidirectional"))
    )
    (net (code "194") (name "unconnected-(IC12-PJ3(PCINT12)-Pad66)") (class "Default")
      (node (ref "IC12") (pin "66") (pinfunction "PJ3(PCINT12)_66") (pintype "bidirectional"))
    )
    (net (code "195") (name "unconnected-(IC12-PJ4(PCINT13)-Pad67)") (class "Default")
      (node (ref "IC12") (pin "67") (pinfunction "PJ4(PCINT13)_67") (pintype "bidirectional"))
    )
    (net (code "196") (name "unconnected-(IC12-PJ5(PCINT14)-Pad68)") (class "Default")
      (node (ref "IC12") (pin "68") (pinfunction "PJ5(PCINT14)_68") (pintype "bidirectional"))
    )
    (net (code "197") (name "unconnected-(IC12-PJ6(PCINT15)-Pad69)") (class "Default")
      (node (ref "IC12") (pin "69") (pinfunction "PJ6(PCINT15)_69") (pintype "bidirectional"))
    )
    (net (code "198") (name "unconnected-(IC12-PJ7-Pad79)") (class "Default")
      (node (ref "IC12") (pin "79") (pinfunction "PJ7_79") (pintype "bidirectional"))
    )
    (net (code "199") (name "unconnected-(IC12-PK6(ADC14{slash}PCINT22)-Pad83)") (class "Default")
      (node (ref "IC12") (pin "83") (pinfunction "PK6(ADC14/PCINT22)_83") (pintype "bidirectional"))
    )
    (net (code "200") (name "unconnected-(IC12-PK7(ADC15{slash}PCINT23)-Pad82)") (class "Default")
      (node (ref "IC12") (pin "82") (pinfunction "PK7(ADC15/PCINT23)_82") (pintype "bidirectional"))
    )
    (net (code "201") (name "unconnected-(IC12-PL0(ICP4)-Pad35)") (class "Default")
      (node (ref "IC12") (pin "35") (pinfunction "PL0(ICP4)_35") (pintype "bidirectional"))
    )
    (net (code "202") (name "unconnected-(U$1-Pad2)") (class "Default")
      (node (ref "U$1") (pin "2") (pinfunction "2_2") (pintype "bidirectional"))
    )
    (net (code "203") (name "unconnected-(U$1-Pad3)") (class "Default")
      (node (ref "U$1") (pin "3") (pinfunction "3_3") (pintype "bidirectional"))
    )
    (net (code "204") (name "unconnected-(U$1-Pad3V3)") (class "Default")
      (node (ref "U$1") (pin "3V3") (pinfunction "3V3_3V3") (pintype "bidirectional"))
    )
    (net (code "205") (name "unconnected-(U$1-Pad4)") (class "Default")
      (node (ref "U$1") (pin "4") (pinfunction "4_4") (pintype "bidirectional"))
    )
    (net (code "206") (name "unconnected-(U$1-Pad5)") (class "Default")
      (node (ref "U$1") (pin "5") (pinfunction "5_5") (pintype "bidirectional"))
    )
    (net (code "207") (name "unconnected-(U$1-Pad6)") (class "Default")
      (node (ref "U$1") (pin "6") (pinfunction "6_6") (pintype "bidirectional"))
    )
    (net (code "208") (name "unconnected-(U$1-Pad7)") (class "Default")
      (node (ref "U$1") (pin "7") (pinfunction "7_7") (pintype "bidirectional"))
    )
    (net (code "209") (name "unconnected-(U$1-Pad8)") (class "Default")
      (node (ref "U$1") (pin "8") (pinfunction "8_8") (pintype "bidirectional"))
    )
    (net (code "210") (name "unconnected-(U$1-Pad9)") (class "Default")
      (node (ref "U$1") (pin "9") (pinfunction "9_9") (pintype "bidirectional"))
    )
    (net (code "211") (name "unconnected-(U$1-Pad10)") (class "Default")
      (node (ref "U$1") (pin "10") (pinfunction "10_10") (pintype "bidirectional"))
    )
    (net (code "212") (name "unconnected-(U$1-Pad11)") (class "Default")
      (node (ref "U$1") (pin "11") (pinfunction "11_11") (pintype "bidirectional"))
    )
    (net (code "213") (name "unconnected-(U$1-Pad12)") (class "Default")
      (node (ref "U$1") (pin "12") (pinfunction "12_12") (pintype "bidirectional"))
    )
    (net (code "214") (name "unconnected-(U$1-Pad13)") (class "Default")
      (node (ref "U$1") (pin "13") (pinfunction "13_13") (pintype "bidirectional"))
    )
    (net (code "215") (name "unconnected-(U$1-PadA0)") (class "Default")
      (node (ref "U$1") (pin "A0") (pinfunction "A0_A0") (pintype "bidirectional"))
    )
    (net (code "216") (name "unconnected-(U$1-PadA1)") (class "Default")
      (node (ref "U$1") (pin "A1") (pinfunction "A1_A1") (pintype "bidirectional"))
    )
    (net (code "217") (name "unconnected-(U$1-PadA2)") (class "Default")
      (node (ref "U$1") (pin "A2") (pinfunction "A2_A2") (pintype "bidirectional"))
    )
    (net (code "218") (name "unconnected-(U$1-PadA3)") (class "Default")
      (node (ref "U$1") (pin "A3") (pinfunction "A3_A3") (pintype "bidirectional"))
    )
    (net (code "219") (name "unconnected-(U$1-PadA4)") (class "Default")
      (node (ref "U$1") (pin "A4") (pinfunction "A4_A4") (pintype "bidirectional"))
    )
    (net (code "220") (name "unconnected-(U$1-PadA5)") (class "Default")
      (node (ref "U$1") (pin "A5") (pinfunction "A5_A5") (pintype "bidirectional"))
    )
    (net (code "221") (name "unconnected-(U$1-PadIOREF)") (class "Default")
      (node (ref "U$1") (pin "IOREF") (pinfunction "IOREF_IOREF") (pintype "bidirectional"))
    )
    (net (code "222") (name "unconnected-(U$1-PadVIN)") (class "Default")
      (node (ref "U$1") (pin "VIN") (pinfunction "VIN_VIN") (pintype "bidirectional"))
    )
    (net (code "223") (name "unconnected-(U$5-Pad6)") (class "Default")
      (node (ref "U$5") (pin "6") (pinfunction "6_6") (pintype "bidirectional"))
    )
    (net (code "224") (name "unconnected-(U$6-Pad6)") (class "Default")
      (node (ref "U$6") (pin "6") (pinfunction "6_6") (pintype "bidirectional"))
    )
    (net (code "225") (name "unconnected-(U$7-Pad6)") (class "Default")
      (node (ref "U$7") (pin "6") (pinfunction "6_6") (pintype "bidirectional"))
    )
    (net (code "226") (name "unconnected-(U$8-Pad6)") (class "Default")
      (node (ref "U$8") (pin "6") (pinfunction "6_6") (pintype "bidirectional"))
    )
    (net (code "227") (name "unconnected-(U$9-Pad6)") (class "Default")
      (node (ref "U$9") (pin "6") (pinfunction "6_6") (pintype "bidirectional"))
    )
    (net (code "228") (name "unconnected-(U$10-Pad6)") (class "Default")
      (node (ref "U$10") (pin "6") (pinfunction "6_6") (pintype "bidirectional"))
    )
    (net (code "229") (name "unconnected-(U$11-Pad6)") (class "Default")
      (node (ref "U$11") (pin "6") (pinfunction "6_6") (pintype "bidirectional"))
    )
    (net (code "230") (name "unconnected-(U$12-Pad6)") (class "Default")
      (node (ref "U$12") (pin "6") (pinfunction "6_6") (pintype "bidirectional"))
    )
    (net (code "231") (name "unconnected-(U$13-Pad6)") (class "Default")
      (node (ref "U$13") (pin "6") (pinfunction "6_6") (pintype "bidirectional"))
    )
    (net (code "232") (name "unconnected-(Z1-C{slash}-Pad2@1)") (class "Default")
      (node (ref "Z1") (pin "2@1") (pinfunction "C/_2@1") (pintype "passive"))
    )
    (net (code "233") (name "unconnected-(Z2-C{slash}-Pad2@1)") (class "Default")
      (node (ref "Z2") (pin "2@1") (pinfunction "C/_2@1") (pintype "passive"))
    )
    (net (code "234") (name "unconnected-(Z3-C{slash}-Pad2@1)") (class "Default")
      (node (ref "Z3") (pin "2@1") (pinfunction "C/_2@1") (pintype "passive"))
    )
    (net (code "235") (name "unconnected-(Z4-C{slash}-Pad2@1)") (class "Default")
      (node (ref "Z4") (pin "2@1") (pinfunction "C/_2@1") (pintype "passive"))
    )
    (net (code "236") (name "unconnected-(Z5-C{slash}-Pad2@1)") (class "Default")
      (node (ref "Z5") (pin "2@1") (pinfunction "C/_2@1") (pintype "passive"))
    )
    (net (code "237") (name "unconnected-(Z6-C{slash}-Pad2@1)") (class "Default")
      (node (ref "Z6") (pin "2@1") (pinfunction "C/_2@1") (pintype "passive"))
    )
    (net (code "238") (name "unconnected-(Z7-C{slash}-Pad2@1)") (class "Default")
      (node (ref "Z7") (pin "2@1") (pinfunction "C/_2@1") (pintype "passive"))
    )
    (net (code "239") (name "unconnected-(Z8-C{slash}-Pad2@1)") (class "Default")
      (node (ref "Z8") (pin "2@1") (pinfunction "C/_2@1") (pintype "passive"))
    )
    (net (code "240") (name "unconnected-(Z9-C{slash}-Pad2@1)") (class "Default")
      (node (ref "Z9") (pin "2@1") (pinfunction "C/_2@1") (pintype "passive"))
    )
  )
)
